# sch_knx-valve-control_v1_0.net
KiCad netlist of a schematic drawn in EasyEDA
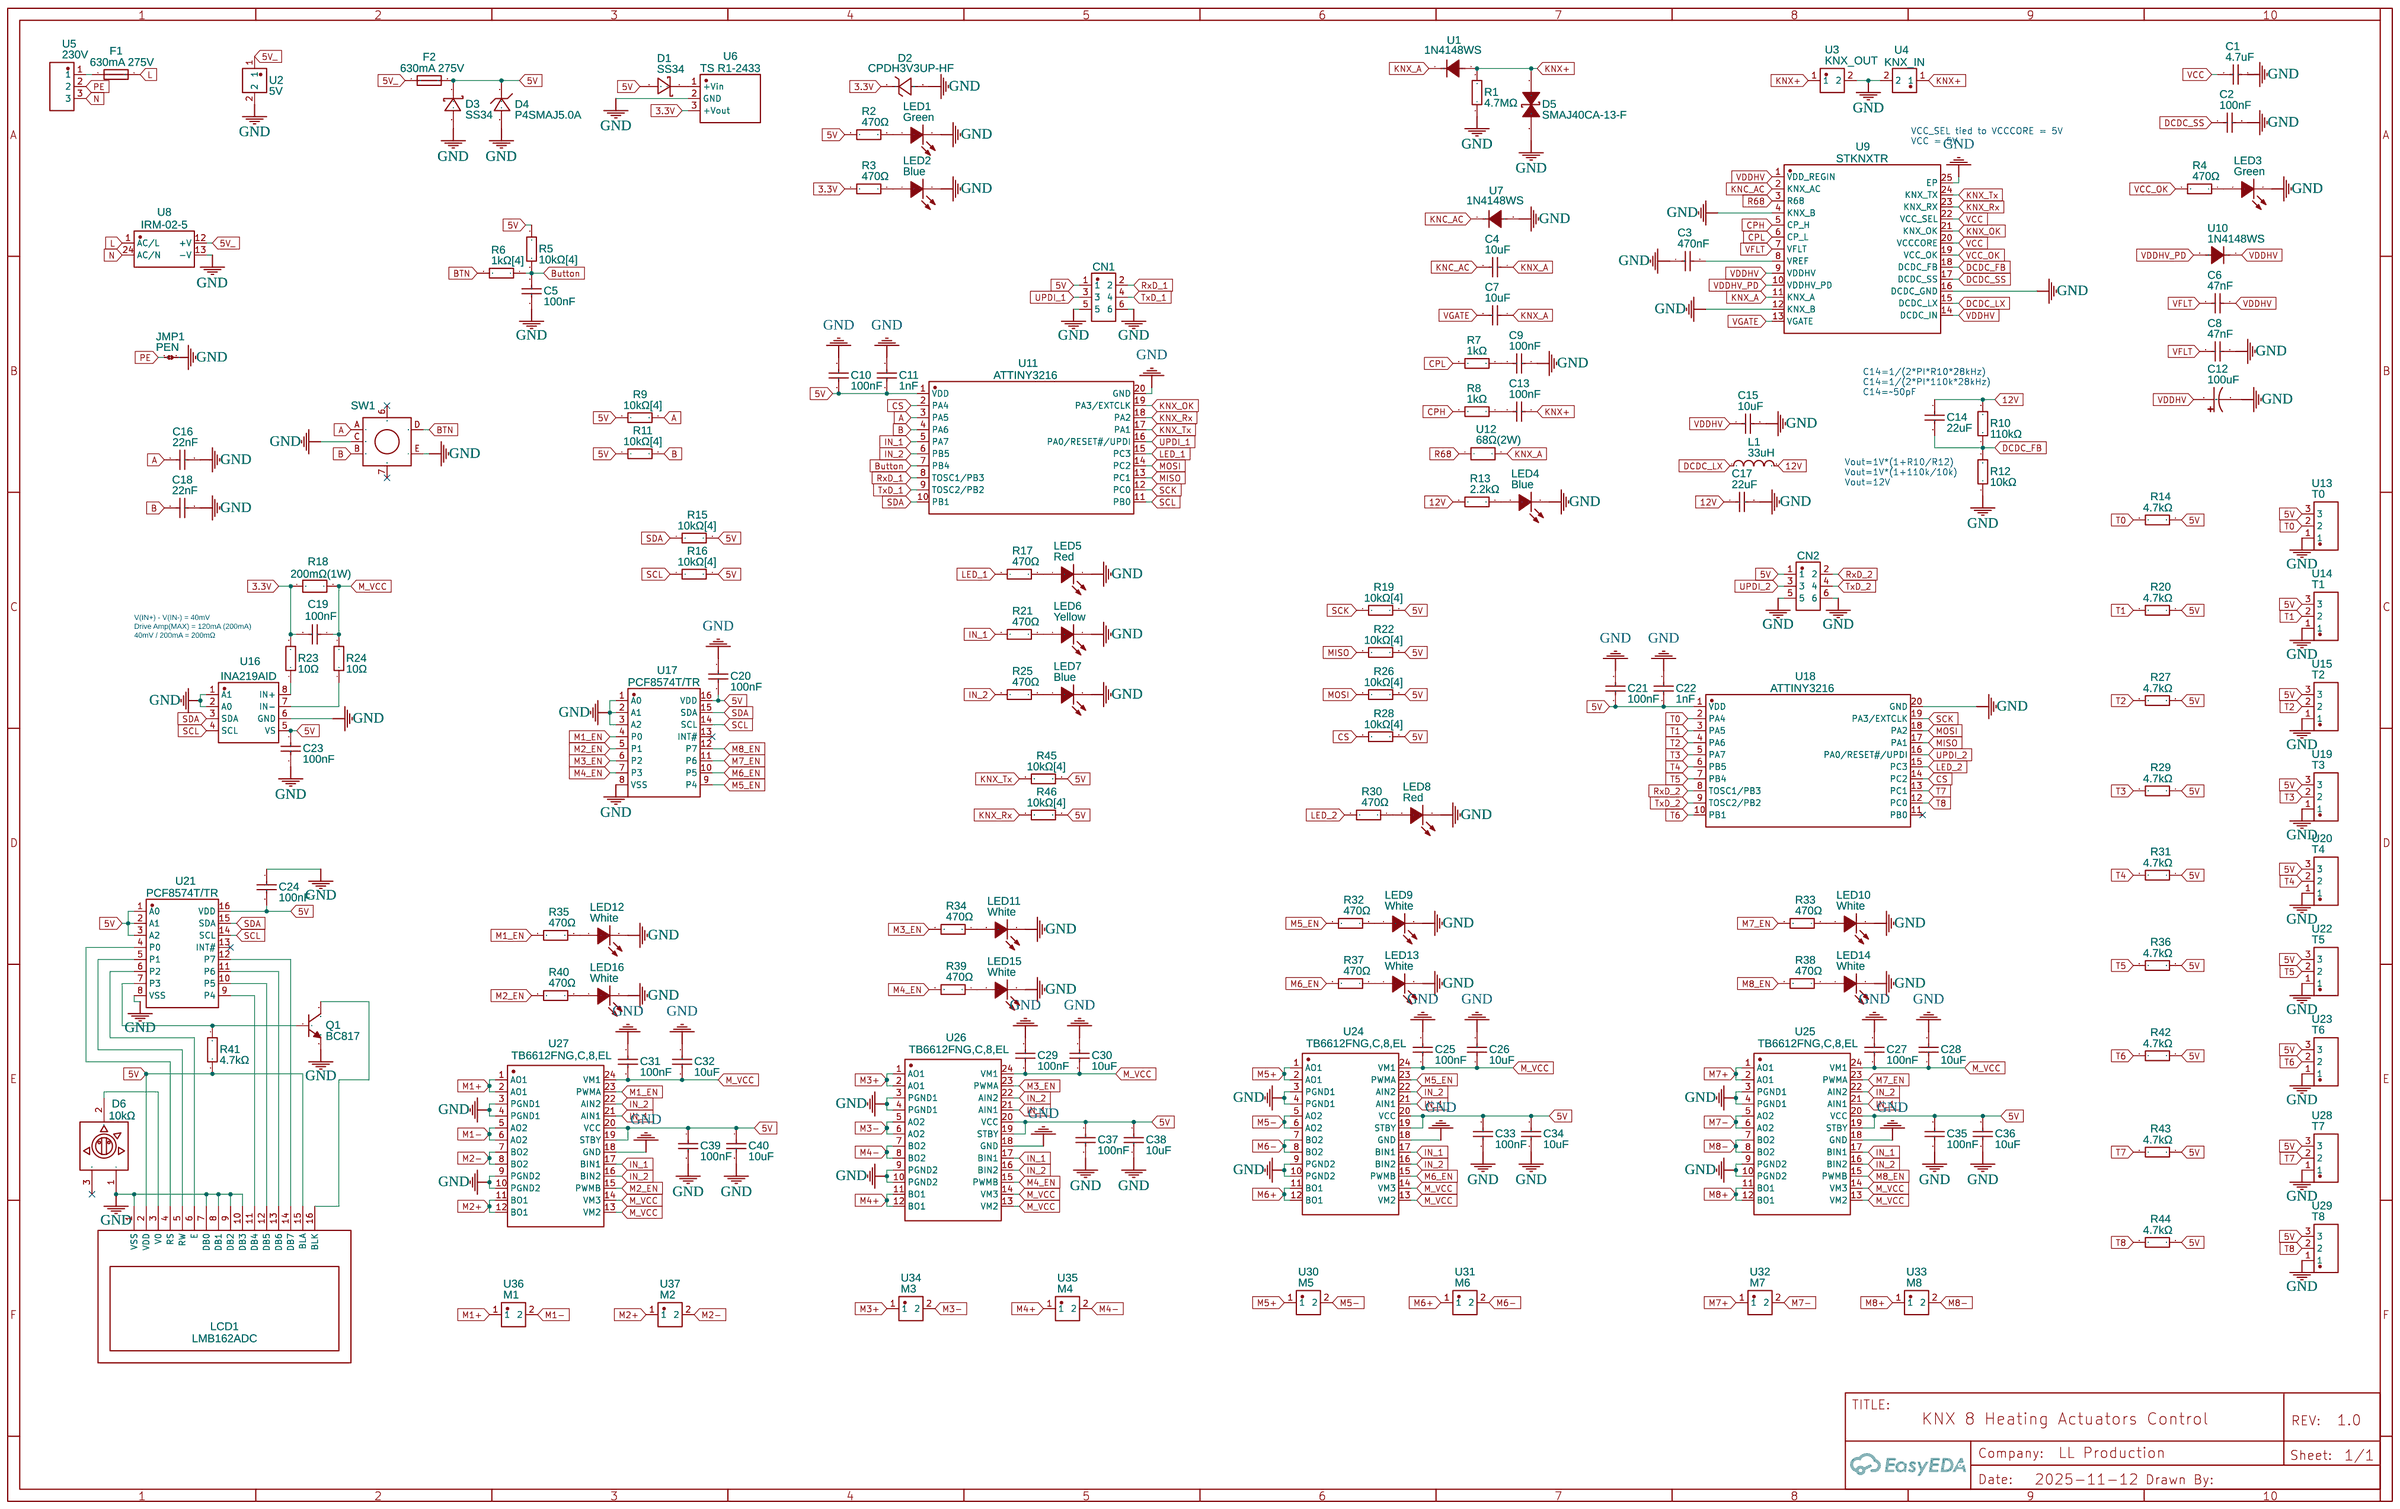
[diagram p0: schematic sheet]

(export (version "E")
  (design (tool "Eeschema 10.0.6"))
  (components
    (comp (ref "C1")
      (value "4.7uF")
      (fields (field (name "Manufacturer Part") "CC0603KRX7R9BB103") (field (name "Manufacturer") "YAGEO"))
      (libsource (lib "") (part "CC0603KRX7R9BB103_1"))
    )
    (comp (ref "C2")
      (value "100nF")
      (fields (field (name "Manufacturer Part") "CC0603KRX7R9BB103") (field (name "Manufacturer") "YAGEO"))
      (libsource (lib "") (part "CC0603KRX7R9BB103_3"))
    )
    (comp (ref "C3")
      (value "470nF")
      (fields (field (name "Manufacturer Part") "CC0603KRX7R9BB103") (field (name "Manufacturer") "YAGEO"))
      (libsource (lib "") (part "CC0603KRX7R9BB103_3"))
    )
    (comp (ref "C4")
      (value "10uF")
      (fields (field (name "Manufacturer Part") "CC0603KRX7R9BB103") (field (name "Manufacturer") "YAGEO"))
      (libsource (lib "") (part "CC0603KRX7R9BB103_1"))
    )
    (comp (ref "C5")
      (value "100nF")
      (fields (field (name "Manufacturer Part") "CC0603KRX7R9BB103") (field (name "Manufacturer") "YAGEO"))
      (libsource (lib "") (part "CC0603KRX7R9BB103_2"))
    )
    (comp (ref "C6")
      (value "47nF")
      (fields (field (name "Manufacturer Part") "CC0603KRX7R9BB103") (field (name "Manufacturer") "YAGEO"))
      (libsource (lib "") (part "CC0603KRX7R9BB103_1"))
    )
    (comp (ref "C7")
      (value "10uF")
      (fields (field (name "Manufacturer Part") "CC0603KRX7R9BB103") (field (name "Manufacturer") "YAGEO"))
      (libsource (lib "") (part "CC0603KRX7R9BB103_1"))
    )
    (comp (ref "C8")
      (value "47nF")
      (fields (field (name "Manufacturer Part") "CC0603KRX7R9BB103") (field (name "Manufacturer") "YAGEO"))
      (libsource (lib "") (part "CC0603KRX7R9BB103_1"))
    )
    (comp (ref "C9")
      (value "100nF")
      (fields (field (name "Manufacturer Part") "CC0603KRX7R9BB103") (field (name "Manufacturer") "YAGEO"))
      (libsource (lib "") (part "CC0603KRX7R9BB103_1"))
    )
    (comp (ref "C10")
      (value "100nF")
      (fields (field (name "Manufacturer Part") "CC0603KRX7R9BB103") (field (name "Manufacturer") "YAGEO"))
      (libsource (lib "") (part "CC0603KRX7R9BB103"))
    )
    (comp (ref "C11")
      (value "1nF")
      (fields (field (name "Manufacturer Part") "CC0603KRX7R9BB103") (field (name "Manufacturer") "YAGEO"))
      (libsource (lib "") (part "CC0603KRX7R9BB103"))
    )
    (comp (ref "C12")
      (value "100uF")
      (fields (field (name "Manufacturer Part") "VEJ101M1HTR-0810") (field (name "Manufacturer") "Lelon(立隆)"))
      (libsource (lib "") (part "VEJ101M1HTR-0810"))
    )
    (comp (ref "C13")
      (value "100nF")
      (fields (field (name "Manufacturer Part") "CC0603KRX7R9BB103") (field (name "Manufacturer") "YAGEO"))
      (libsource (lib "") (part "CC0603KRX7R9BB103_1"))
    )
    (comp (ref "C14")
      (value "22uF")
      (fields (field (name "Manufacturer Part") "CC0603KRX7R9BB103") (field (name "Manufacturer") "YAGEO"))
      (libsource (lib "") (part "CC0603KRX7R9BB103_2"))
    )
    (comp (ref "C15")
      (value "10uF")
      (fields (field (name "Manufacturer Part") "CC0603KRX7R9BB103") (field (name "Manufacturer") "YAGEO"))
      (libsource (lib "") (part "CC0603KRX7R9BB103_3"))
    )
    (comp (ref "C16")
      (value "22nF")
      (fields (field (name "Manufacturer Part") "CC0603KRX7R9BB103") (field (name "Manufacturer") "YAGEO"))
      (libsource (lib "") (part "CC0603KRX7R9BB103_1"))
    )
    (comp (ref "C17")
      (value "22uF")
      (fields (field (name "Manufacturer Part") "CC0603KRX7R9BB103") (field (name "Manufacturer") "YAGEO"))
      (libsource (lib "") (part "CC0603KRX7R9BB103_3"))
    )
    (comp (ref "C18")
      (value "22nF")
      (fields (field (name "Manufacturer Part") "CC0603KRX7R9BB103") (field (name "Manufacturer") "YAGEO"))
      (libsource (lib "") (part "CC0603KRX7R9BB103_1"))
    )
    (comp (ref "C19")
      (value "100nF")
      (fields (field (name "Manufacturer Part") "CC0603KRX7R9BB103") (field (name "Manufacturer") "YAGEO"))
      (libsource (lib "") (part "CC0603KRX7R9BB103_1"))
    )
    (comp (ref "C20")
      (value "100nF")
      (fields (field (name "Manufacturer Part") "CC0603KRX7R9BB103") (field (name "Manufacturer") "YAGEO"))
      (libsource (lib "") (part "CC0603KRX7R9BB103_2"))
    )
    (comp (ref "C21")
      (value "100nF")
      (fields (field (name "Manufacturer Part") "CC0603KRX7R9BB103") (field (name "Manufacturer") "YAGEO"))
      (libsource (lib "") (part "CC0603KRX7R9BB103"))
    )
    (comp (ref "C22")
      (value "1nF")
      (fields (field (name "Manufacturer Part") "CC0603KRX7R9BB103") (field (name "Manufacturer") "YAGEO"))
      (libsource (lib "") (part "CC0603KRX7R9BB103"))
    )
    (comp (ref "C23")
      (value "100nF")
      (fields (field (name "Manufacturer Part") "CC0603KRX7R9BB103") (field (name "Manufacturer") "YAGEO"))
      (libsource (lib "") (part "CC0603KRX7R9BB103_2"))
    )
    (comp (ref "C24")
      (value "100nF")
      (fields (field (name "Manufacturer Part") "CC0603KRX7R9BB103") (field (name "Manufacturer") "YAGEO"))
      (libsource (lib "") (part "CC0603KRX7R9BB103_2"))
    )
    (comp (ref "C25")
      (value "100nF")
      (fields (field (name "Manufacturer Part") "CC0603KRX7R9BB103") (field (name "Manufacturer") "YAGEO"))
      (libsource (lib "") (part "CC0603KRX7R9BB103_2"))
    )
    (comp (ref "C26")
      (value "10uF")
      (fields (field (name "Manufacturer Part") "CC0603KRX7R9BB103") (field (name "Manufacturer") "YAGEO"))
      (libsource (lib "") (part "CC0603KRX7R9BB103_2"))
    )
    (comp (ref "C27")
      (value "100nF")
      (fields (field (name "Manufacturer Part") "CC0603KRX7R9BB103") (field (name "Manufacturer") "YAGEO"))
      (libsource (lib "") (part "CC0603KRX7R9BB103_2"))
    )
    (comp (ref "C28")
      (value "10uF")
      (fields (field (name "Manufacturer Part") "CC0603KRX7R9BB103") (field (name "Manufacturer") "YAGEO"))
      (libsource (lib "") (part "CC0603KRX7R9BB103_2"))
    )
    (comp (ref "C29")
      (value "100nF")
      (fields (field (name "Manufacturer Part") "CC0603KRX7R9BB103") (field (name "Manufacturer") "YAGEO"))
      (libsource (lib "") (part "CC0603KRX7R9BB103_2"))
    )
    (comp (ref "C30")
      (value "10uF")
      (fields (field (name "Manufacturer Part") "CC0603KRX7R9BB103") (field (name "Manufacturer") "YAGEO"))
      (libsource (lib "") (part "CC0603KRX7R9BB103_2"))
    )
    (comp (ref "C31")
      (value "100nF")
      (fields (field (name "Manufacturer Part") "CC0603KRX7R9BB103") (field (name "Manufacturer") "YAGEO"))
      (libsource (lib "") (part "CC0603KRX7R9BB103_2"))
    )
    (comp (ref "C32")
      (value "10uF")
      (fields (field (name "Manufacturer Part") "CC0603KRX7R9BB103") (field (name "Manufacturer") "YAGEO"))
      (libsource (lib "") (part "CC0603KRX7R9BB103_2"))
    )
    (comp (ref "C33")
      (value "100nF")
      (fields (field (name "Manufacturer Part") "CC0603KRX7R9BB103") (field (name "Manufacturer") "YAGEO"))
      (libsource (lib "") (part "CC0603KRX7R9BB103_2"))
    )
    (comp (ref "C34")
      (value "10uF")
      (fields (field (name "Manufacturer Part") "CC0603KRX7R9BB103") (field (name "Manufacturer") "YAGEO"))
      (libsource (lib "") (part "CC0603KRX7R9BB103_2"))
    )
    (comp (ref "C35")
      (value "100nF")
      (fields (field (name "Manufacturer Part") "CC0603KRX7R9BB103") (field (name "Manufacturer") "YAGEO"))
      (libsource (lib "") (part "CC0603KRX7R9BB103_2"))
    )
    (comp (ref "C36")
      (value "10uF")
      (fields (field (name "Manufacturer Part") "CC0603KRX7R9BB103") (field (name "Manufacturer") "YAGEO"))
      (libsource (lib "") (part "CC0603KRX7R9BB103_2"))
    )
    (comp (ref "C37")
      (value "100nF")
      (fields (field (name "Manufacturer Part") "CC0603KRX7R9BB103") (field (name "Manufacturer") "YAGEO"))
      (libsource (lib "") (part "CC0603KRX7R9BB103_2"))
    )
    (comp (ref "C38")
      (value "10uF")
      (fields (field (name "Manufacturer Part") "CC0603KRX7R9BB103") (field (name "Manufacturer") "YAGEO"))
      (libsource (lib "") (part "CC0603KRX7R9BB103_2"))
    )
    (comp (ref "C39")
      (value "100nF")
      (fields (field (name "Manufacturer Part") "CC0603KRX7R9BB103") (field (name "Manufacturer") "YAGEO"))
      (libsource (lib "") (part "CC0603KRX7R9BB103_2"))
    )
    (comp (ref "C40")
      (value "10uF")
      (fields (field (name "Manufacturer Part") "CC0603KRX7R9BB103") (field (name "Manufacturer") "YAGEO"))
      (libsource (lib "") (part "CC0603KRX7R9BB103_2"))
    )
    (comp (ref "CN1")
      (value "321006SG0ABK00A01")
      (fields (field (name "Manufacturer") "JILN(锦凌)"))
      (libsource (lib "") (part "321006SG0ABK00A01"))
    )
    (comp (ref "CN2")
      (value "321006SG0ABK00A01")
      (fields (field (name "Manufacturer") "JILN(锦凌)"))
      (libsource (lib "") (part "321006SG0ABK00A01"))
    )
    (comp (ref "D1")
      (value "SS34")
      (fields (field (name "Manufacturer") "MDD"))
      (libsource (lib "") (part "SS34_C8678_1"))
    )
    (comp (ref "D2")
      (value "CPDH3V3UP-HF")
      (fields (field (name "Manufacturer Part") "SOD-523"))
      (libsource (lib "") (part "SOD-523"))
    )
    (comp (ref "D3")
      (value "SS34")
      (fields (field (name "Manufacturer") "MDD"))
      (libsource (lib "") (part "SS34_C8678"))
    )
    (comp (ref "D4")
      (value "P4SMAJ5.0A")
      (fields
        (field (name "Manufacturer Part") "P4SMAJ12A_R1_00001")
        (field (name "Manufacturer") "PANJIT(强茂)")
      )
      (libsource (lib "") (part "P4SMAJ12A-PEC"))
    )
    (comp (ref "D5")
      (value "SMAJ40CA-13-F")
      (fields (field (name "Manufacturer") "DIODES(美台)"))
      (libsource (lib "") (part "SMAJ40CA-13-F"))
    )
    (comp (ref "D6")
      (value "10kΩ")
      (fields (field (name "Manufacturer Part") "3314G-1-103E") (field (name "Manufacturer") "BOURNS"))
      (libsource (lib "") (part "3314G-1-103E"))
    )
    (comp (ref "F1")
      (value "630mA 275V")
      (fields (field (name "Manufacturer Part") "S1032-F-60.0A") (field (name "Manufacturer") "SART(萨特)"))
      (libsource (lib "") (part "S1032-F-60.0A"))
    )
    (comp (ref "F2")
      (value "630mA 275V")
      (fields (field (name "Manufacturer Part") "S1032-F-60.0A") (field (name "Manufacturer") "SART(萨特)"))
      (libsource (lib "") (part "S1032-F-60.0A"))
    )
    (comp (ref "JMP1") (value "PEN") (libsource (lib "") (part "JMP-2-NO-0603")))
    (comp (ref "L1")
      (value "33uH")
      (fields
        (field (name "Manufacturer Part") "NR5040T330M")
        (field (name "Manufacturer") "TAIYO YUDEN(太诱)")
      )
      (libsource (lib "") (part "NR5040T330M"))
    )
    (comp (ref "LCD1")
      (value "LMB162ADC")
      (fields (field (name "Manufacturer") "TOPWAY"))
      (libsource (lib "") (part "LMB162ADC"))
    )
    (comp (ref "LED1")
      (value "Green")
      (fields (field (name "Manufacturer Part") "SZYY0603R") (field (name "Manufacturer") "yongyu(永裕光电)"))
      (libsource (lib "") (part "SZYY0603R"))
    )
    (comp (ref "LED2")
      (value "Blue")
      (fields (field (name "Manufacturer Part") "SZYY0603R") (field (name "Manufacturer") "yongyu(永裕光电)"))
      (libsource (lib "") (part "SZYY0603R"))
    )
    (comp (ref "LED3")
      (value "Green")
      (fields (field (name "Manufacturer Part") "SZYY0603R") (field (name "Manufacturer") "yongyu(永裕光电)"))
      (libsource (lib "") (part "SZYY0603R"))
    )
    (comp (ref "LED4")
      (value "Blue")
      (fields (field (name "Manufacturer Part") "SZYY0603R") (field (name "Manufacturer") "yongyu(永裕光电)"))
      (libsource (lib "") (part "SZYY0603R"))
    )
    (comp (ref "LED5")
      (value "Red")
      (fields (field (name "Manufacturer Part") "SZYY0603R") (field (name "Manufacturer") "yongyu(永裕光电)"))
      (libsource (lib "") (part "SZYY0603R"))
    )
    (comp (ref "LED6")
      (value "Yellow")
      (fields (field (name "Manufacturer Part") "SZYY0603R") (field (name "Manufacturer") "yongyu(永裕光电)"))
      (libsource (lib "") (part "SZYY0603R"))
    )
    (comp (ref "LED7")
      (value "Blue")
      (fields (field (name "Manufacturer Part") "SZYY0603R") (field (name "Manufacturer") "yongyu(永裕光电)"))
      (libsource (lib "") (part "SZYY0603R"))
    )
    (comp (ref "LED8")
      (value "Red")
      (fields (field (name "Manufacturer Part") "SZYY0603R") (field (name "Manufacturer") "yongyu(永裕光电)"))
      (libsource (lib "") (part "SZYY0603R"))
    )
    (comp (ref "LED9")
      (value "White")
      (fields (field (name "Manufacturer Part") "SZYY0603R") (field (name "Manufacturer") "yongyu(永裕光电)"))
      (libsource (lib "") (part "SZYY0603R"))
    )
    (comp (ref "LED10")
      (value "White")
      (fields (field (name "Manufacturer Part") "SZYY0603R") (field (name "Manufacturer") "yongyu(永裕光电)"))
      (libsource (lib "") (part "SZYY0603R"))
    )
    (comp (ref "LED11")
      (value "White")
      (fields (field (name "Manufacturer Part") "SZYY0603R") (field (name "Manufacturer") "yongyu(永裕光电)"))
      (libsource (lib "") (part "SZYY0603R"))
    )
    (comp (ref "LED12")
      (value "White")
      (fields (field (name "Manufacturer Part") "SZYY0603R") (field (name "Manufacturer") "yongyu(永裕光电)"))
      (libsource (lib "") (part "SZYY0603R"))
    )
    (comp (ref "LED13")
      (value "White")
      (fields (field (name "Manufacturer Part") "SZYY0603R") (field (name "Manufacturer") "yongyu(永裕光电)"))
      (libsource (lib "") (part "SZYY0603R"))
    )
    (comp (ref "LED14")
      (value "White")
      (fields (field (name "Manufacturer Part") "SZYY0603R") (field (name "Manufacturer") "yongyu(永裕光电)"))
      (libsource (lib "") (part "SZYY0603R"))
    )
    (comp (ref "LED15")
      (value "White")
      (fields (field (name "Manufacturer Part") "SZYY0603R") (field (name "Manufacturer") "yongyu(永裕光电)"))
      (libsource (lib "") (part "SZYY0603R"))
    )
    (comp (ref "LED16")
      (value "White")
      (fields (field (name "Manufacturer Part") "SZYY0603R") (field (name "Manufacturer") "yongyu(永裕光电)"))
      (libsource (lib "") (part "SZYY0603R"))
    )
    (comp (ref "Q1")
      (value "BC817")
      (fields (field (name "Manufacturer Part") "BC817-40,215") (field (name "Manufacturer") "Nexperia(安世)"))
      (libsource (lib "") (part "BC817-40,215"))
    )
    (comp (ref "R1")
      (value "4.7MΩ")
      (fields (field (name "Manufacturer Part") "CR0603FA1001G") (field (name "Manufacturer") "LIZ(丽智电子)"))
      (libsource (lib "") (part "CR0603FA1001G_C126900_1"))
    )
    (comp (ref "R2")
      (value "470Ω")
      (fields (field (name "Manufacturer Part") "CR0603FA1001G") (field (name "Manufacturer") "LIZ(丽智电子)"))
      (libsource (lib "") (part "CR0603FA1001G_C126900"))
    )
    (comp (ref "R3")
      (value "470Ω")
      (fields (field (name "Manufacturer Part") "CR0603FA1001G") (field (name "Manufacturer") "LIZ(丽智电子)"))
      (libsource (lib "") (part "CR0603FA1001G_C126900"))
    )
    (comp (ref "R4")
      (value "470Ω")
      (fields (field (name "Manufacturer Part") "CR0603FA1001G") (field (name "Manufacturer") "LIZ(丽智电子)"))
      (libsource (lib "") (part "CR0603FA1001G_C126900"))
    )
    (comp (ref "R5")
      (value "10kΩ[4]")
      (fields
        (field (name "Manufacturer Part") "0402WGF1002TCE")
        (field (name "Manufacturer") "UNI-ROYAL(厚声)")
      )
      (libsource (lib "") (part "0402WGF1002TCE_2"))
    )
    (comp (ref "R6")
      (value "1kΩ[4]")
      (fields
        (field (name "Manufacturer Part") "0402WGF1002TCE")
        (field (name "Manufacturer") "UNI-ROYAL(厚声)")
      )
      (libsource (lib "") (part "0402WGF1002TCE_1"))
    )
    (comp (ref "R7")
      (value "1kΩ")
      (fields (field (name "Manufacturer Part") "CR0603FA1001G") (field (name "Manufacturer") "LIZ(丽智电子)"))
      (libsource (lib "") (part "CR0603FA1001G_C126900"))
    )
    (comp (ref "R8")
      (value "1kΩ")
      (fields (field (name "Manufacturer Part") "CR0603FA1001G") (field (name "Manufacturer") "LIZ(丽智电子)"))
      (libsource (lib "") (part "CR0603FA1001G_C126900"))
    )
    (comp (ref "R9")
      (value "10kΩ[4]")
      (fields
        (field (name "Manufacturer Part") "0402WGF1002TCE")
        (field (name "Manufacturer") "UNI-ROYAL(厚声)")
      )
      (libsource (lib "") (part "0402WGF1002TCE"))
    )
    (comp (ref "R10")
      (value "110kΩ")
      (fields (field (name "Manufacturer Part") "CR0603FA1001G") (field (name "Manufacturer") "LIZ(丽智电子)"))
      (libsource (lib "") (part "CR0603FA1001G_C126900_1"))
    )
    (comp (ref "R11")
      (value "10kΩ[4]")
      (fields
        (field (name "Manufacturer Part") "0402WGF1002TCE")
        (field (name "Manufacturer") "UNI-ROYAL(厚声)")
      )
      (libsource (lib "") (part "0402WGF1002TCE"))
    )
    (comp (ref "R12")
      (value "10kΩ")
      (fields (field (name "Manufacturer Part") "CR0603FA1001G") (field (name "Manufacturer") "LIZ(丽智电子)"))
      (libsource (lib "") (part "CR0603FA1001G_C126900_1"))
    )
    (comp (ref "R13")
      (value "2.2kΩ")
      (fields (field (name "Manufacturer Part") "CR0603FA1001G") (field (name "Manufacturer") "LIZ(丽智电子)"))
      (libsource (lib "") (part "CR0603FA1001G_C126900"))
    )
    (comp (ref "R14")
      (value "4.7kΩ")
      (fields (field (name "Manufacturer Part") "CR0603FA1001G") (field (name "Manufacturer") "LIZ(丽智电子)"))
      (libsource (lib "") (part "CR0603FA1001G_C126900"))
    )
    (comp (ref "R15")
      (value "10kΩ[4]")
      (fields
        (field (name "Manufacturer Part") "0402WGF1002TCE")
        (field (name "Manufacturer") "UNI-ROYAL(厚声)")
      )
      (libsource (lib "") (part "0402WGF1002TCE"))
    )
    (comp (ref "R16")
      (value "10kΩ[4]")
      (fields
        (field (name "Manufacturer Part") "0402WGF1002TCE")
        (field (name "Manufacturer") "UNI-ROYAL(厚声)")
      )
      (libsource (lib "") (part "0402WGF1002TCE"))
    )
    (comp (ref "R17")
      (value "470Ω")
      (fields (field (name "Manufacturer Part") "CR0603FA1001G") (field (name "Manufacturer") "LIZ(丽智电子)"))
      (libsource (lib "") (part "CR0603FA1001G_C126900"))
    )
    (comp (ref "R18")
      (value "200mΩ(1W)")
      (fields (field (name "Manufacturer Part") "SCR1206F1M1") (field (name "Manufacturer") "VO(翔胜)"))
      (libsource (lib "") (part "SCR1206F1M1"))
    )
    (comp (ref "R19")
      (value "10kΩ[4]")
      (fields
        (field (name "Manufacturer Part") "0402WGF1002TCE")
        (field (name "Manufacturer") "UNI-ROYAL(厚声)")
      )
      (libsource (lib "") (part "0402WGF1002TCE"))
    )
    (comp (ref "R20")
      (value "4.7kΩ")
      (fields (field (name "Manufacturer Part") "CR0603FA1001G") (field (name "Manufacturer") "LIZ(丽智电子)"))
      (libsource (lib "") (part "CR0603FA1001G_C126900"))
    )
    (comp (ref "R21")
      (value "470Ω")
      (fields (field (name "Manufacturer Part") "CR0603FA1001G") (field (name "Manufacturer") "LIZ(丽智电子)"))
      (libsource (lib "") (part "CR0603FA1001G_C126900"))
    )
    (comp (ref "R22")
      (value "10kΩ[4]")
      (fields
        (field (name "Manufacturer Part") "0402WGF1002TCE")
        (field (name "Manufacturer") "UNI-ROYAL(厚声)")
      )
      (libsource (lib "") (part "0402WGF1002TCE"))
    )
    (comp (ref "R23")
      (value "10Ω")
      (fields (field (name "Manufacturer Part") "CR0603FA1001G") (field (name "Manufacturer") "LIZ(丽智电子)"))
      (libsource (lib "") (part "CR0603FA1001G_C126900_1"))
    )
    (comp (ref "R24")
      (value "10Ω")
      (fields (field (name "Manufacturer Part") "CR0603FA1001G") (field (name "Manufacturer") "LIZ(丽智电子)"))
      (libsource (lib "") (part "CR0603FA1001G_C126900_1"))
    )
    (comp (ref "R25")
      (value "470Ω")
      (fields (field (name "Manufacturer Part") "CR0603FA1001G") (field (name "Manufacturer") "LIZ(丽智电子)"))
      (libsource (lib "") (part "CR0603FA1001G_C126900"))
    )
    (comp (ref "R26")
      (value "10kΩ[4]")
      (fields
        (field (name "Manufacturer Part") "0402WGF1002TCE")
        (field (name "Manufacturer") "UNI-ROYAL(厚声)")
      )
      (libsource (lib "") (part "0402WGF1002TCE"))
    )
    (comp (ref "R27")
      (value "4.7kΩ")
      (fields (field (name "Manufacturer Part") "CR0603FA1001G") (field (name "Manufacturer") "LIZ(丽智电子)"))
      (libsource (lib "") (part "CR0603FA1001G_C126900"))
    )
    (comp (ref "R28")
      (value "10kΩ[4]")
      (fields
        (field (name "Manufacturer Part") "0402WGF1002TCE")
        (field (name "Manufacturer") "UNI-ROYAL(厚声)")
      )
      (libsource (lib "") (part "0402WGF1002TCE"))
    )
    (comp (ref "R29")
      (value "4.7kΩ")
      (fields (field (name "Manufacturer Part") "CR0603FA1001G") (field (name "Manufacturer") "LIZ(丽智电子)"))
      (libsource (lib "") (part "CR0603FA1001G_C126900"))
    )
    (comp (ref "R30")
      (value "470Ω")
      (fields (field (name "Manufacturer Part") "CR0603FA1001G") (field (name "Manufacturer") "LIZ(丽智电子)"))
      (libsource (lib "") (part "CR0603FA1001G_C126900"))
    )
    (comp (ref "R31")
      (value "4.7kΩ")
      (fields (field (name "Manufacturer Part") "CR0603FA1001G") (field (name "Manufacturer") "LIZ(丽智电子)"))
      (libsource (lib "") (part "CR0603FA1001G_C126900"))
    )
    (comp (ref "R32")
      (value "470Ω")
      (fields (field (name "Manufacturer Part") "CR0603FA1001G") (field (name "Manufacturer") "LIZ(丽智电子)"))
      (libsource (lib "") (part "CR0603FA1001G_C126900"))
    )
    (comp (ref "R33")
      (value "470Ω")
      (fields (field (name "Manufacturer Part") "CR0603FA1001G") (field (name "Manufacturer") "LIZ(丽智电子)"))
      (libsource (lib "") (part "CR0603FA1001G_C126900"))
    )
    (comp (ref "R34")
      (value "470Ω")
      (fields (field (name "Manufacturer Part") "CR0603FA1001G") (field (name "Manufacturer") "LIZ(丽智电子)"))
      (libsource (lib "") (part "CR0603FA1001G_C126900"))
    )
    (comp (ref "R35")
      (value "470Ω")
      (fields (field (name "Manufacturer Part") "CR0603FA1001G") (field (name "Manufacturer") "LIZ(丽智电子)"))
      (libsource (lib "") (part "CR0603FA1001G_C126900"))
    )
    (comp (ref "R36")
      (value "4.7kΩ")
      (fields (field (name "Manufacturer Part") "CR0603FA1001G") (field (name "Manufacturer") "LIZ(丽智电子)"))
      (libsource (lib "") (part "CR0603FA1001G_C126900"))
    )
    (comp (ref "R37")
      (value "470Ω")
      (fields (field (name "Manufacturer Part") "CR0603FA1001G") (field (name "Manufacturer") "LIZ(丽智电子)"))
      (libsource (lib "") (part "CR0603FA1001G_C126900"))
    )
    (comp (ref "R38")
      (value "470Ω")
      (fields (field (name "Manufacturer Part") "CR0603FA1001G") (field (name "Manufacturer") "LIZ(丽智电子)"))
      (libsource (lib "") (part "CR0603FA1001G_C126900"))
    )
    (comp (ref "R39")
      (value "470Ω")
      (fields (field (name "Manufacturer Part") "CR0603FA1001G") (field (name "Manufacturer") "LIZ(丽智电子)"))
      (libsource (lib "") (part "CR0603FA1001G_C126900"))
    )
    (comp (ref "R40")
      (value "470Ω")
      (fields (field (name "Manufacturer Part") "CR0603FA1001G") (field (name "Manufacturer") "LIZ(丽智电子)"))
      (libsource (lib "") (part "CR0603FA1001G_C126900"))
    )
    (comp (ref "R41")
      (value "4.7kΩ")
      (fields (field (name "Manufacturer Part") "CR0603FA1001G") (field (name "Manufacturer") "LIZ(丽智电子)"))
      (libsource (lib "") (part "CR0603FA1001G_C126900_2"))
    )
    (comp (ref "R42")
      (value "4.7kΩ")
      (fields (field (name "Manufacturer Part") "CR0603FA1001G") (field (name "Manufacturer") "LIZ(丽智电子)"))
      (libsource (lib "") (part "CR0603FA1001G_C126900"))
    )
    (comp (ref "R43")
      (value "4.7kΩ")
      (fields (field (name "Manufacturer Part") "CR0603FA1001G") (field (name "Manufacturer") "LIZ(丽智电子)"))
      (libsource (lib "") (part "CR0603FA1001G_C126900"))
    )
    (comp (ref "R44")
      (value "4.7kΩ")
      (fields (field (name "Manufacturer Part") "CR0603FA1001G") (field (name "Manufacturer") "LIZ(丽智电子)"))
      (libsource (lib "") (part "CR0603FA1001G_C126900"))
    )
    (comp (ref "R45")
      (value "10kΩ[4]")
      (fields
        (field (name "Manufacturer Part") "0402WGF1002TCE")
        (field (name "Manufacturer") "UNI-ROYAL(厚声)")
      )
      (libsource (lib "") (part "0402WGF1002TCE"))
    )
    (comp (ref "R46")
      (value "10kΩ[4]")
      (fields
        (field (name "Manufacturer Part") "0402WGF1002TCE")
        (field (name "Manufacturer") "UNI-ROYAL(厚声)")
      )
      (libsource (lib "") (part "0402WGF1002TCE"))
    )
    (comp (ref "SW1")
      (value "EC11L1525G01")
      (fields (field (name "Manufacturer") "ALPSALPINE(阿尔卑斯阿尔派)"))
      (libsource (lib "") (part "EC11L1525G01"))
    )
    (comp (ref "U1")
      (value "1N4148WS")
      (fields (field (name "Manufacturer") "Zhengxin(正芯)"))
      (libsource (lib "") (part "1N4148WS"))
    )
    (comp (ref "U2")
      (value "5V")
      (fields (field (name "Manufacturer Part") "2P,间距5.08mm,弹片压线升降式"))
      (libsource (lib "") (part "2P,间距5.08MM,弹片压线升降式_1"))
    )
    (comp (ref "U3")
      (value "KNX_OUT")
      (fields (field (name "Manufacturer Part") "2P,间距5.08mm,弹片压线升降式"))
      (libsource (lib "") (part "2P,间距5.08MM,弹片压线升降式"))
    )
    (comp (ref "U4")
      (value "KNX_IN")
      (fields (field (name "Manufacturer Part") "2P,间距5.08mm,弹片压线升降式"))
      (libsource (lib "") (part "2P,间距5.08MM,弹片压线升降式_2"))
    )
    (comp (ref "U5")
      (value "230V")
      (fields
        (field (name "Manufacturer Part") "DB127V-5.08-3P-GN-S")
        (field (name "Manufacturer") "DIBO(地博电气)")
      )
      (libsource (lib "") (part "DB127V-5.08-3P-GN-S_1"))
    )
    (comp (ref "U6")
      (value "TS R1-2433")
      (fields (field (name "Manufacturer") "TRACO POWER"))
      (libsource (lib "") (part "TS R1-2433"))
    )
    (comp (ref "U7")
      (value "1N4148WS")
      (fields (field (name "Manufacturer") "Zhengxin(正芯)"))
      (libsource (lib "") (part "1N4148WS"))
    )
    (comp (ref "U8")
      (value "IRM-02-5")
      (fields (field (name "Manufacturer") "MW(明纬)"))
      (libsource (lib "") (part "IRM-02-5"))
    )
    (comp (ref "U9")
      (value "STKNXTR")
      (fields (field (name "Manufacturer") "ST(意法半导体)"))
      (libsource (lib "") (part "STKNXTR"))
    )
    (comp (ref "U10")
      (value "1N4148WS")
      (fields (field (name "Manufacturer") "Zhengxin(正芯)"))
      (libsource (lib "") (part "1N4148WS_1"))
    )
    (comp (ref "U11")
      (value "ATTINY3216")
      (fields
        (field (name "Manufacturer Part") "ATTINY1616-SN")
        (field (name "Manufacturer") "MICROCHIP(美国微芯)")
      )
      (libsource (lib "") (part "ATTINY1616-SN_C614136"))
    )
    (comp (ref "U12")
      (value "68Ω(2W)")
      (fields
        (field (name "Manufacturer Part") "HoJLR2512-3W-3.5mR-1%")
        (field (name "Manufacturer") "Milliohm(毫欧)")
      )
      (libsource (lib "") (part "HOJLR2512-3W-3.5MR-1%"))
    )
    (comp (ref "U13")
      (value "T0")
      (fields
        (field (name "Manufacturer Part") "DB127V-5.08-3P-GN-S")
        (field (name "Manufacturer") "DIBO(地博电气)")
      )
      (libsource (lib "") (part "DB127V-5.08-3P-GN-S"))
    )
    (comp (ref "U14")
      (value "T1")
      (fields
        (field (name "Manufacturer Part") "DB127V-5.08-3P-GN-S")
        (field (name "Manufacturer") "DIBO(地博电气)")
      )
      (libsource (lib "") (part "DB127V-5.08-3P-GN-S"))
    )
    (comp (ref "U15")
      (value "T2")
      (fields
        (field (name "Manufacturer Part") "DB127V-5.08-3P-GN-S")
        (field (name "Manufacturer") "DIBO(地博电气)")
      )
      (libsource (lib "") (part "DB127V-5.08-3P-GN-S"))
    )
    (comp (ref "U16")
      (value "INA219AID")
      (fields (field (name "Manufacturer") "TI(德州仪器)"))
      (libsource (lib "") (part "INA219AID"))
    )
    (comp (ref "U17")
      (value "PCF8574T/TR")
      (fields (field (name "Manufacturer") "HGSEMI(华冠)"))
      (libsource (lib "") (part "PCF8574T/TR"))
    )
    (comp (ref "U18")
      (value "ATTINY3216")
      (fields
        (field (name "Manufacturer Part") "ATTINY1616-SN")
        (field (name "Manufacturer") "MICROCHIP(美国微芯)")
      )
      (libsource (lib "") (part "ATTINY1616-SN_C614136"))
    )
    (comp (ref "U19")
      (value "T3")
      (fields
        (field (name "Manufacturer Part") "DB127V-5.08-3P-GN-S")
        (field (name "Manufacturer") "DIBO(地博电气)")
      )
      (libsource (lib "") (part "DB127V-5.08-3P-GN-S"))
    )
    (comp (ref "U20")
      (value "T4")
      (fields
        (field (name "Manufacturer Part") "DB127V-5.08-3P-GN-S")
        (field (name "Manufacturer") "DIBO(地博电气)")
      )
      (libsource (lib "") (part "DB127V-5.08-3P-GN-S"))
    )
    (comp (ref "U21")
      (value "PCF8574T/TR")
      (fields (field (name "Manufacturer") "HGSEMI(华冠)"))
      (libsource (lib "") (part "PCF8574T/TR"))
    )
    (comp (ref "U22")
      (value "T5")
      (fields
        (field (name "Manufacturer Part") "DB127V-5.08-3P-GN-S")
        (field (name "Manufacturer") "DIBO(地博电气)")
      )
      (libsource (lib "") (part "DB127V-5.08-3P-GN-S"))
    )
    (comp (ref "U23")
      (value "T6")
      (fields
        (field (name "Manufacturer Part") "DB127V-5.08-3P-GN-S")
        (field (name "Manufacturer") "DIBO(地博电气)")
      )
      (libsource (lib "") (part "DB127V-5.08-3P-GN-S"))
    )
    (comp (ref "U24")
      (value "TB6612FNG,C,8,EL")
      (fields (field (name "Manufacturer") "TOSHIBA(东芝)"))
      (libsource (lib "") (part "TB6612FNG,C,8,EL"))
    )
    (comp (ref "U25")
      (value "TB6612FNG,C,8,EL")
      (fields (field (name "Manufacturer") "TOSHIBA(东芝)"))
      (libsource (lib "") (part "TB6612FNG,C,8,EL"))
    )
    (comp (ref "U26")
      (value "TB6612FNG,C,8,EL")
      (fields (field (name "Manufacturer") "TOSHIBA(东芝)"))
      (libsource (lib "") (part "TB6612FNG,C,8,EL"))
    )
    (comp (ref "U27")
      (value "TB6612FNG,C,8,EL")
      (fields (field (name "Manufacturer") "TOSHIBA(东芝)"))
      (libsource (lib "") (part "TB6612FNG,C,8,EL"))
    )
    (comp (ref "U28")
      (value "T7")
      (fields
        (field (name "Manufacturer Part") "DB127V-5.08-3P-GN-S")
        (field (name "Manufacturer") "DIBO(地博电气)")
      )
      (libsource (lib "") (part "DB127V-5.08-3P-GN-S"))
    )
    (comp (ref "U29")
      (value "T8")
      (fields
        (field (name "Manufacturer Part") "DB127V-5.08-3P-GN-S")
        (field (name "Manufacturer") "DIBO(地博电气)")
      )
      (libsource (lib "") (part "DB127V-5.08-3P-GN-S"))
    )
    (comp (ref "U30")
      (value "M5")
      (fields (field (name "Manufacturer Part") "2P,间距5.08mm,弹片压线升降式"))
      (libsource (lib "") (part "2P,间距5.08MM,弹片压线升降式"))
    )
    (comp (ref "U31")
      (value "M6")
      (fields (field (name "Manufacturer Part") "2P,间距5.08mm,弹片压线升降式"))
      (libsource (lib "") (part "2P,间距5.08MM,弹片压线升降式"))
    )
    (comp (ref "U32")
      (value "M7")
      (fields (field (name "Manufacturer Part") "2P,间距5.08mm,弹片压线升降式"))
      (libsource (lib "") (part "2P,间距5.08MM,弹片压线升降式"))
    )
    (comp (ref "U33")
      (value "M8")
      (fields (field (name "Manufacturer Part") "2P,间距5.08mm,弹片压线升降式"))
      (libsource (lib "") (part "2P,间距5.08MM,弹片压线升降式"))
    )
    (comp (ref "U34")
      (value "M3")
      (fields (field (name "Manufacturer Part") "2P,间距5.08mm,弹片压线升降式"))
      (libsource (lib "") (part "2P,间距5.08MM,弹片压线升降式"))
    )
    (comp (ref "U35")
      (value "M4")
      (fields (field (name "Manufacturer Part") "2P,间距5.08mm,弹片压线升降式"))
      (libsource (lib "") (part "2P,间距5.08MM,弹片压线升降式"))
    )
    (comp (ref "U36")
      (value "M1")
      (fields (field (name "Manufacturer Part") "2P,间距5.08mm,弹片压线升降式"))
      (libsource (lib "") (part "2P,间距5.08MM,弹片压线升降式"))
    )
    (comp (ref "U37")
      (value "M2")
      (fields (field (name "Manufacturer Part") "2P,间距5.08mm,弹片压线升降式"))
      (libsource (lib "") (part "2P,间距5.08MM,弹片压线升降式"))
    )
  )
  (nets
    (net (code "1") (name "3.3V") (class "Default")
      (node (ref "C19") (pin "2") (pinfunction "2_2") (pintype "input"))
      (node (ref "D2") (pin "1") (pinfunction "K_1") (pintype "unspecified"))
      (node (ref "R18") (pin "1") (pinfunction "1_1") (pintype "unspecified"))
      (node (ref "R23") (pin "2") (pinfunction "2_2") (pintype "input"))
      (node (ref "R3") (pin "2") (pinfunction "2_2") (pintype "input"))
      (node (ref "U6") (pin "3") (pinfunction "+Vout_3") (pintype "unspecified"))
    )
    (net (code "2") (name "5V") (class "Default")
      (node (ref "C10") (pin "1") (pinfunction "1_1") (pintype "input"))
      (node (ref "C11") (pin "1") (pinfunction "1_1") (pintype "input"))
      (node (ref "C20") (pin "2") (pinfunction "2_2") (pintype "input"))
      (node (ref "C21") (pin "1") (pinfunction "1_1") (pintype "input"))
      (node (ref "C22") (pin "1") (pinfunction "1_1") (pintype "input"))
      (node (ref "C23") (pin "1") (pinfunction "1_1") (pintype "input"))
      (node (ref "C24") (pin "2") (pinfunction "2_2") (pintype "input"))
      (node (ref "C33") (pin "1") (pinfunction "1_1") (pintype "input"))
      (node (ref "C34") (pin "1") (pinfunction "1_1") (pintype "input"))
      (node (ref "C35") (pin "1") (pinfunction "1_1") (pintype "input"))
      (node (ref "C36") (pin "1") (pinfunction "1_1") (pintype "input"))
      (node (ref "C37") (pin "1") (pinfunction "1_1") (pintype "input"))
      (node (ref "C38") (pin "1") (pinfunction "1_1") (pintype "input"))
      (node (ref "C39") (pin "1") (pinfunction "1_1") (pintype "input"))
      (node (ref "C40") (pin "1") (pinfunction "1_1") (pintype "input"))
      (node (ref "CN1") (pin "1") (pinfunction "1_1") (pintype "unspecified"))
      (node (ref "CN2") (pin "1") (pinfunction "1_1") (pintype "unspecified"))
      (node (ref "D1") (pin "2") (pinfunction "A_2") (pintype "unspecified"))
      (node (ref "D3") (pin "1") (pinfunction "K_1") (pintype "unspecified"))
      (node (ref "D4") (pin "1") (pinfunction "C_1") (pintype "unspecified"))
      (node (ref "F2") (pin "2") (pinfunction "2_2") (pintype "unspecified"))
      (node (ref "LCD1") (pin "15") (pinfunction "BLA_15") (pintype "unspecified"))
      (node (ref "LCD1") (pin "2") (pinfunction "VDD_2") (pintype "unspecified"))
      (node (ref "R11") (pin "1") (pinfunction "1_1") (pintype "input"))
      (node (ref "R14") (pin "1") (pinfunction "1_1") (pintype "input"))
      (node (ref "R15") (pin "2") (pinfunction "2_2") (pintype "input"))
      (node (ref "R16") (pin "2") (pinfunction "2_2") (pintype "input"))
      (node (ref "R19") (pin "2") (pinfunction "2_2") (pintype "input"))
      (node (ref "R2") (pin "2") (pinfunction "2_2") (pintype "input"))
      (node (ref "R20") (pin "1") (pinfunction "1_1") (pintype "input"))
      (node (ref "R22") (pin "2") (pinfunction "2_2") (pintype "input"))
      (node (ref "R26") (pin "2") (pinfunction "2_2") (pintype "input"))
      (node (ref "R27") (pin "1") (pinfunction "1_1") (pintype "input"))
      (node (ref "R28") (pin "2") (pinfunction "2_2") (pintype "input"))
      (node (ref "R29") (pin "1") (pinfunction "1_1") (pintype "input"))
      (node (ref "R31") (pin "1") (pinfunction "1_1") (pintype "input"))
      (node (ref "R36") (pin "1") (pinfunction "1_1") (pintype "input"))
      (node (ref "R41") (pin "2") (pinfunction "2_2") (pintype "input"))
      (node (ref "R42") (pin "1") (pinfunction "1_1") (pintype "input"))
      (node (ref "R43") (pin "1") (pinfunction "1_1") (pintype "input"))
      (node (ref "R44") (pin "1") (pinfunction "1_1") (pintype "input"))
      (node (ref "R45") (pin "2") (pinfunction "2_2") (pintype "input"))
      (node (ref "R46") (pin "2") (pinfunction "2_2") (pintype "input"))
      (node (ref "R5") (pin "1") (pinfunction "1_1") (pintype "input"))
      (node (ref "R9") (pin "1") (pinfunction "1_1") (pintype "input"))
      (node (ref "U11") (pin "1") (pinfunction "VDD_1") (pintype "unspecified"))
      (node (ref "U13") (pin "3") (pinfunction "3_3") (pintype "unspecified"))
      (node (ref "U14") (pin "3") (pinfunction "3_3") (pintype "unspecified"))
      (node (ref "U15") (pin "3") (pinfunction "3_3") (pintype "unspecified"))
      (node (ref "U16") (pin "5") (pinfunction "VS_5") (pintype "unspecified"))
      (node (ref "U17") (pin "16") (pinfunction "VDD_16") (pintype "unspecified"))
      (node (ref "U18") (pin "1") (pinfunction "VDD_1") (pintype "unspecified"))
      (node (ref "U19") (pin "3") (pinfunction "3_3") (pintype "unspecified"))
      (node (ref "U20") (pin "3") (pinfunction "3_3") (pintype "unspecified"))
      (node (ref "U21") (pin "1") (pinfunction "A0_1") (pintype "unspecified"))
      (node (ref "U21") (pin "16") (pinfunction "VDD_16") (pintype "unspecified"))
      (node (ref "U21") (pin "2") (pinfunction "A1_2") (pintype "unspecified"))
      (node (ref "U21") (pin "3") (pinfunction "A2_3") (pintype "unspecified"))
      (node (ref "U22") (pin "3") (pinfunction "3_3") (pintype "unspecified"))
      (node (ref "U23") (pin "3") (pinfunction "3_3") (pintype "unspecified"))
      (node (ref "U24") (pin "19") (pinfunction "STBY_19") (pintype "unspecified"))
      (node (ref "U24") (pin "20") (pinfunction "VCC_20") (pintype "unspecified"))
      (node (ref "U25") (pin "19") (pinfunction "STBY_19") (pintype "unspecified"))
      (node (ref "U25") (pin "20") (pinfunction "VCC_20") (pintype "unspecified"))
      (node (ref "U26") (pin "19") (pinfunction "STBY_19") (pintype "unspecified"))
      (node (ref "U26") (pin "20") (pinfunction "VCC_20") (pintype "unspecified"))
      (node (ref "U27") (pin "19") (pinfunction "STBY_19") (pintype "unspecified"))
      (node (ref "U27") (pin "20") (pinfunction "VCC_20") (pintype "unspecified"))
      (node (ref "U28") (pin "3") (pinfunction "3_3") (pintype "unspecified"))
      (node (ref "U29") (pin "3") (pinfunction "3_3") (pintype "unspecified"))
    )
    (net (code "3") (name "5V_") (class "Default")
      (node (ref "F2") (pin "1") (pinfunction "1_1") (pintype "unspecified"))
      (node (ref "U2") (pin "1") (pinfunction "1_1") (pintype "unspecified"))
      (node (ref "U8") (pin "12") (pinfunction "+V_12") (pintype "unspecified"))
    )
    (net (code "4") (name "12V") (class "Default")
      (node (ref "C14") (pin "1") (pinfunction "1_1") (pintype "input"))
      (node (ref "C17") (pin "1") (pinfunction "1_1") (pintype "input"))
      (node (ref "L1") (pin "2") (pinfunction "2_2") (pintype "unspecified"))
      (node (ref "R10") (pin "2") (pinfunction "2_2") (pintype "input"))
      (node (ref "R13") (pin "2") (pinfunction "2_2") (pintype "input"))
    )
    (net (code "5") (name "A") (class "Default")
      (node (ref "C16") (pin "2") (pinfunction "2_2") (pintype "input"))
      (node (ref "R9") (pin "2") (pinfunction "2_2") (pintype "input"))
      (node (ref "SW1") (pin "A") (pinfunction "A_A") (pintype "unspecified"))
      (node (ref "U11") (pin "3") (pinfunction "PA5_3") (pintype "unspecified"))
    )
    (net (code "6") (name "B") (class "Default")
      (node (ref "C18") (pin "2") (pinfunction "2_2") (pintype "input"))
      (node (ref "R11") (pin "2") (pinfunction "2_2") (pintype "input"))
      (node (ref "SW1") (pin "B") (pinfunction "B_B") (pintype "unspecified"))
      (node (ref "U11") (pin "4") (pinfunction "PA6_4") (pintype "unspecified"))
    )
    (net (code "7") (name "BTN") (class "Default")
      (node (ref "R6") (pin "2") (pinfunction "2_2") (pintype "input"))
      (node (ref "SW1") (pin "D") (pinfunction "D_D") (pintype "unspecified"))
    )
    (net (code "8") (name "Button") (class "Default")
      (node (ref "C5") (pin "1") (pinfunction "1_1") (pintype "input"))
      (node (ref "R5") (pin "2") (pinfunction "2_2") (pintype "input"))
      (node (ref "R6") (pin "1") (pinfunction "1_1") (pintype "input"))
      (node (ref "U11") (pin "7") (pinfunction "PB4_7") (pintype "unspecified"))
    )
    (net (code "9") (name "CPH") (class "Default")
      (node (ref "R8") (pin "2") (pinfunction "2_2") (pintype "input"))
      (node (ref "U9") (pin "5") (pinfunction "CP_H_5") (pintype "unspecified"))
    )
    (net (code "10") (name "CPL") (class "Default")
      (node (ref "R7") (pin "2") (pinfunction "2_2") (pintype "input"))
      (node (ref "U9") (pin "6") (pinfunction "CP_L_6") (pintype "unspecified"))
    )
    (net (code "11") (name "CS") (class "Default")
      (node (ref "R28") (pin "1") (pinfunction "1_1") (pintype "input"))
      (node (ref "U11") (pin "2") (pinfunction "PA4_2") (pintype "unspecified"))
      (node (ref "U18") (pin "14") (pinfunction "PC2_14") (pintype "unspecified"))
    )
    (net (code "12") (name "DCDC_FB") (class "Default")
      (node (ref "C14") (pin "2") (pinfunction "2_2") (pintype "input"))
      (node (ref "R10") (pin "1") (pinfunction "1_1") (pintype "input"))
      (node (ref "R12") (pin "2") (pinfunction "2_2") (pintype "input"))
      (node (ref "U9") (pin "18") (pinfunction "DCDC_FB_18") (pintype "unspecified"))
    )
    (net (code "13") (name "DCDC_LX") (class "Default")
      (node (ref "L1") (pin "1") (pinfunction "1_1") (pintype "unspecified"))
      (node (ref "U9") (pin "15") (pinfunction "DCDC_LX_15") (pintype "unspecified"))
    )
    (net (code "14") (name "DCDC_SS") (class "Default")
      (node (ref "C2") (pin "1") (pinfunction "1_1") (pintype "input"))
      (node (ref "U9") (pin "17") (pinfunction "DCDC_SS_17") (pintype "unspecified"))
    )
    (net (code "15") (name "GND") (class "Default")
      (node (ref "C1") (pin "1") (pinfunction "1_1") (pintype "input"))
      (node (ref "C10") (pin "2") (pinfunction "2_2") (pintype "input"))
      (node (ref "C11") (pin "2") (pinfunction "2_2") (pintype "input"))
      (node (ref "C12") (pin "2") (pinfunction "2_2") (pintype "unspecified"))
      (node (ref "C15") (pin "2") (pinfunction "2_2") (pintype "input"))
      (node (ref "C16") (pin "1") (pinfunction "1_1") (pintype "input"))
      (node (ref "C17") (pin "2") (pinfunction "2_2") (pintype "input"))
      (node (ref "C18") (pin "1") (pinfunction "1_1") (pintype "input"))
      (node (ref "C2") (pin "2") (pinfunction "2_2") (pintype "input"))
      (node (ref "C20") (pin "1") (pinfunction "1_1") (pintype "input"))
      (node (ref "C21") (pin "2") (pinfunction "2_2") (pintype "input"))
      (node (ref "C22") (pin "2") (pinfunction "2_2") (pintype "input"))
      (node (ref "C23") (pin "2") (pinfunction "2_2") (pintype "input"))
      (node (ref "C24") (pin "1") (pinfunction "1_1") (pintype "input"))
      (node (ref "C25") (pin "1") (pinfunction "1_1") (pintype "input"))
      (node (ref "C26") (pin "1") (pinfunction "1_1") (pintype "input"))
      (node (ref "C27") (pin "1") (pinfunction "1_1") (pintype "input"))
      (node (ref "C28") (pin "1") (pinfunction "1_1") (pintype "input"))
      (node (ref "C29") (pin "1") (pinfunction "1_1") (pintype "input"))
      (node (ref "C3") (pin "1") (pinfunction "1_1") (pintype "input"))
      (node (ref "C30") (pin "1") (pinfunction "1_1") (pintype "input"))
      (node (ref "C31") (pin "1") (pinfunction "1_1") (pintype "input"))
      (node (ref "C32") (pin "1") (pinfunction "1_1") (pintype "input"))
      (node (ref "C33") (pin "2") (pinfunction "2_2") (pintype "input"))
      (node (ref "C34") (pin "2") (pinfunction "2_2") (pintype "input"))
      (node (ref "C35") (pin "2") (pinfunction "2_2") (pintype "input"))
      (node (ref "C36") (pin "2") (pinfunction "2_2") (pintype "input"))
      (node (ref "C37") (pin "2") (pinfunction "2_2") (pintype "input"))
      (node (ref "C38") (pin "2") (pinfunction "2_2") (pintype "input"))
      (node (ref "C39") (pin "2") (pinfunction "2_2") (pintype "input"))
      (node (ref "C40") (pin "2") (pinfunction "2_2") (pintype "input"))
      (node (ref "C5") (pin "2") (pinfunction "2_2") (pintype "input"))
      (node (ref "C8") (pin "1") (pinfunction "1_1") (pintype "input"))
      (node (ref "C9") (pin "1") (pinfunction "1_1") (pintype "input"))
      (node (ref "CN1") (pin "5") (pinfunction "5_5") (pintype "unspecified"))
      (node (ref "CN1") (pin "6") (pinfunction "6_6") (pintype "unspecified"))
      (node (ref "CN2") (pin "5") (pinfunction "5_5") (pintype "unspecified"))
      (node (ref "CN2") (pin "6") (pinfunction "6_6") (pintype "unspecified"))
      (node (ref "D2") (pin "2") (pinfunction "A_2") (pintype "unspecified"))
      (node (ref "D3") (pin "2") (pinfunction "A_2") (pintype "unspecified"))
      (node (ref "D4") (pin "2") (pinfunction "A_2") (pintype "unspecified"))
      (node (ref "D5") (pin "2") (pinfunction "2_2") (pintype "unspecified"))
      (node (ref "D6") (pin "1") (pinfunction "1_1") (pintype "unspecified"))
      (node (ref "JMP1") (pin "2") (pinfunction "2_2") (pintype "unspecified"))
      (node (ref "LCD1") (pin "1") (pinfunction "VSS_1") (pintype "unspecified"))
      (node (ref "LCD1") (pin "10") (pinfunction "DB3_10") (pintype "unspecified"))
      (node (ref "LCD1") (pin "7") (pinfunction "DB0_7") (pintype "unspecified"))
      (node (ref "LCD1") (pin "8") (pinfunction "DB1_8") (pintype "unspecified"))
      (node (ref "LCD1") (pin "9") (pinfunction "DB2_9") (pintype "unspecified"))
      (node (ref "LED1") (pin "2") (pinfunction "-_2") (pintype "unspecified"))
      (node (ref "LED10") (pin "2") (pinfunction "-_2") (pintype "unspecified"))
      (node (ref "LED11") (pin "2") (pinfunction "-_2") (pintype "unspecified"))
      (node (ref "LED12") (pin "2") (pinfunction "-_2") (pintype "unspecified"))
      (node (ref "LED13") (pin "2") (pinfunction "-_2") (pintype "unspecified"))
      (node (ref "LED14") (pin "2") (pinfunction "-_2") (pintype "unspecified"))
      (node (ref "LED15") (pin "2") (pinfunction "-_2") (pintype "unspecified"))
      (node (ref "LED16") (pin "2") (pinfunction "-_2") (pintype "unspecified"))
      (node (ref "LED2") (pin "2") (pinfunction "-_2") (pintype "unspecified"))
      (node (ref "LED3") (pin "2") (pinfunction "-_2") (pintype "unspecified"))
      (node (ref "LED4") (pin "2") (pinfunction "-_2") (pintype "unspecified"))
      (node (ref "LED5") (pin "2") (pinfunction "-_2") (pintype "unspecified"))
      (node (ref "LED6") (pin "2") (pinfunction "-_2") (pintype "unspecified"))
      (node (ref "LED7") (pin "2") (pinfunction "-_2") (pintype "unspecified"))
      (node (ref "LED8") (pin "2") (pinfunction "-_2") (pintype "unspecified"))
      (node (ref "LED9") (pin "2") (pinfunction "-_2") (pintype "unspecified"))
      (node (ref "Q1") (pin "2") (pinfunction "2_2") (pintype "input"))
      (node (ref "R1") (pin "1") (pinfunction "1_1") (pintype "input"))
      (node (ref "R12") (pin "1") (pinfunction "1_1") (pintype "input"))
      (node (ref "SW1") (pin "C") (pinfunction "C_C") (pintype "unspecified"))
      (node (ref "SW1") (pin "E") (pinfunction "E_E") (pintype "unspecified"))
      (node (ref "U11") (pin "20") (pinfunction "GND_20") (pintype "unspecified"))
      (node (ref "U13") (pin "1") (pinfunction "1_1") (pintype "unspecified"))
      (node (ref "U14") (pin "1") (pinfunction "1_1") (pintype "unspecified"))
      (node (ref "U15") (pin "1") (pinfunction "1_1") (pintype "unspecified"))
      (node (ref "U16") (pin "1") (pinfunction "A1_1") (pintype "unspecified"))
      (node (ref "U16") (pin "2") (pinfunction "A0_2") (pintype "unspecified"))
      (node (ref "U16") (pin "6") (pinfunction "GND_6") (pintype "unspecified"))
      (node (ref "U17") (pin "1") (pinfunction "A0_1") (pintype "unspecified"))
      (node (ref "U17") (pin "2") (pinfunction "A1_2") (pintype "unspecified"))
      (node (ref "U17") (pin "3") (pinfunction "A2_3") (pintype "unspecified"))
      (node (ref "U17") (pin "8") (pinfunction "VSS_8") (pintype "unspecified"))
      (node (ref "U18") (pin "20") (pinfunction "GND_20") (pintype "unspecified"))
      (node (ref "U19") (pin "1") (pinfunction "1_1") (pintype "unspecified"))
      (node (ref "U2") (pin "2") (pinfunction "2_2") (pintype "unspecified"))
      (node (ref "U20") (pin "1") (pinfunction "1_1") (pintype "unspecified"))
      (node (ref "U21") (pin "8") (pinfunction "VSS_8") (pintype "unspecified"))
      (node (ref "U22") (pin "1") (pinfunction "1_1") (pintype "unspecified"))
      (node (ref "U23") (pin "1") (pinfunction "1_1") (pintype "unspecified"))
      (node (ref "U24") (pin "10") (pinfunction "PGND2_10") (pintype "unspecified"))
      (node (ref "U24") (pin "18") (pinfunction "GND_18") (pintype "unspecified"))
      (node (ref "U24") (pin "3") (pinfunction "PGND1_3") (pintype "unspecified"))
      (node (ref "U24") (pin "4") (pinfunction "PGND1_4") (pintype "unspecified"))
      (node (ref "U24") (pin "9") (pinfunction "PGND2_9") (pintype "unspecified"))
      (node (ref "U25") (pin "10") (pinfunction "PGND2_10") (pintype "unspecified"))
      (node (ref "U25") (pin "18") (pinfunction "GND_18") (pintype "unspecified"))
      (node (ref "U25") (pin "3") (pinfunction "PGND1_3") (pintype "unspecified"))
      (node (ref "U25") (pin "4") (pinfunction "PGND1_4") (pintype "unspecified"))
      (node (ref "U25") (pin "9") (pinfunction "PGND2_9") (pintype "unspecified"))
      (node (ref "U26") (pin "10") (pinfunction "PGND2_10") (pintype "unspecified"))
      (node (ref "U26") (pin "18") (pinfunction "GND_18") (pintype "unspecified"))
      (node (ref "U26") (pin "3") (pinfunction "PGND1_3") (pintype "unspecified"))
      (node (ref "U26") (pin "4") (pinfunction "PGND1_4") (pintype "unspecified"))
      (node (ref "U26") (pin "9") (pinfunction "PGND2_9") (pintype "unspecified"))
      (node (ref "U27") (pin "10") (pinfunction "PGND2_10") (pintype "unspecified"))
      (node (ref "U27") (pin "18") (pinfunction "GND_18") (pintype "unspecified"))
      (node (ref "U27") (pin "3") (pinfunction "PGND1_3") (pintype "unspecified"))
      (node (ref "U27") (pin "4") (pinfunction "PGND1_4") (pintype "unspecified"))
      (node (ref "U27") (pin "9") (pinfunction "PGND2_9") (pintype "unspecified"))
      (node (ref "U28") (pin "1") (pinfunction "1_1") (pintype "unspecified"))
      (node (ref "U29") (pin "1") (pinfunction "1_1") (pintype "unspecified"))
      (node (ref "U3") (pin "2") (pinfunction "2_2") (pintype "unspecified"))
      (node (ref "U4") (pin "2") (pinfunction "2_2") (pintype "unspecified"))
      (node (ref "U6") (pin "2") (pinfunction "GND_2") (pintype "unspecified"))
      (node (ref "U7") (pin "2") (pinfunction "A_2") (pintype "unspecified"))
      (node (ref "U8") (pin "13") (pinfunction "-V_13") (pintype "unspecified"))
      (node (ref "U9") (pin "12") (pinfunction "KNX_B_12") (pintype "unspecified"))
      (node (ref "U9") (pin "16") (pinfunction "DCDC_GND_16") (pintype "unspecified"))
      (node (ref "U9") (pin "25") (pinfunction "EP_25") (pintype "unspecified"))
      (node (ref "U9") (pin "4") (pinfunction "KNX_B_4") (pintype "unspecified"))
    )
    (net (code "16") (name "IN_1") (class "Default")
      (node (ref "R21") (pin "2") (pinfunction "2_2") (pintype "input"))
      (node (ref "U11") (pin "5") (pinfunction "PA7_5") (pintype "unspecified"))
      (node (ref "U24") (pin "17") (pinfunction "BIN1_17") (pintype "unspecified"))
      (node (ref "U24") (pin "21") (pinfunction "AIN1_21") (pintype "unspecified"))
      (node (ref "U25") (pin "17") (pinfunction "BIN1_17") (pintype "unspecified"))
      (node (ref "U25") (pin "21") (pinfunction "AIN1_21") (pintype "unspecified"))
      (node (ref "U26") (pin "17") (pinfunction "BIN1_17") (pintype "unspecified"))
      (node (ref "U26") (pin "21") (pinfunction "AIN1_21") (pintype "unspecified"))
      (node (ref "U27") (pin "17") (pinfunction "BIN1_17") (pintype "unspecified"))
      (node (ref "U27") (pin "21") (pinfunction "AIN1_21") (pintype "unspecified"))
    )
    (net (code "17") (name "IN_2") (class "Default")
      (node (ref "R25") (pin "2") (pinfunction "2_2") (pintype "input"))
      (node (ref "U11") (pin "6") (pinfunction "PB5_6") (pintype "unspecified"))
      (node (ref "U24") (pin "16") (pinfunction "BIN2_16") (pintype "unspecified"))
      (node (ref "U24") (pin "22") (pinfunction "AIN2_22") (pintype "unspecified"))
      (node (ref "U25") (pin "16") (pinfunction "BIN2_16") (pintype "unspecified"))
      (node (ref "U25") (pin "22") (pinfunction "AIN2_22") (pintype "unspecified"))
      (node (ref "U26") (pin "16") (pinfunction "BIN2_16") (pintype "unspecified"))
      (node (ref "U26") (pin "22") (pinfunction "AIN2_22") (pintype "unspecified"))
      (node (ref "U27") (pin "16") (pinfunction "BIN2_16") (pintype "unspecified"))
      (node (ref "U27") (pin "22") (pinfunction "AIN2_22") (pintype "unspecified"))
    )
    (net (code "18") (name "KNC_AC") (class "Default")
      (node (ref "C4") (pin "2") (pinfunction "2_2") (pintype "input"))
      (node (ref "U7") (pin "1") (pinfunction "K_1") (pintype "unspecified"))
      (node (ref "U9") (pin "2") (pinfunction "KNX_AC_2") (pintype "unspecified"))
    )
    (net (code "19") (name "KNX+") (class "Default")
      (node (ref "C13") (pin "1") (pinfunction "1_1") (pintype "input"))
      (node (ref "D5") (pin "1") (pinfunction "1_1") (pintype "unspecified"))
      (node (ref "R1") (pin "2") (pinfunction "2_2") (pintype "input"))
      (node (ref "U1") (pin "2") (pinfunction "A_2") (pintype "unspecified"))
      (node (ref "U3") (pin "1") (pinfunction "1_1") (pintype "unspecified"))
      (node (ref "U4") (pin "1") (pinfunction "1_1") (pintype "unspecified"))
    )
    (net (code "20") (name "KNX_A") (class "Default")
      (node (ref "C4") (pin "1") (pinfunction "1_1") (pintype "input"))
      (node (ref "C7") (pin "1") (pinfunction "1_1") (pintype "input"))
      (node (ref "U1") (pin "1") (pinfunction "K_1") (pintype "unspecified"))
      (node (ref "U12") (pin "2") (pinfunction "2_2") (pintype "unspecified"))
      (node (ref "U9") (pin "11") (pinfunction "KNX_A_11") (pintype "unspecified"))
    )
    (net (code "21") (name "KNX_OK") (class "Default")
      (node (ref "U11") (pin "19") (pinfunction "PA3/EXTCLK_19") (pintype "unspecified"))
      (node (ref "U9") (pin "21") (pinfunction "KNX_OK_21") (pintype "unspecified"))
    )
    (net (code "22") (name "KNX_Rx") (class "Default")
      (node (ref "R46") (pin "1") (pinfunction "1_1") (pintype "input"))
      (node (ref "U11") (pin "18") (pinfunction "PA2_18") (pintype "unspecified"))
      (node (ref "U9") (pin "23") (pinfunction "KNX_RX_23") (pintype "unspecified"))
    )
    (net (code "23") (name "KNX_Tx") (class "Default")
      (node (ref "R45") (pin "1") (pinfunction "1_1") (pintype "input"))
      (node (ref "U11") (pin "17") (pinfunction "PA1_17") (pintype "unspecified"))
      (node (ref "U9") (pin "24") (pinfunction "KNX_TX_24") (pintype "unspecified"))
    )
    (net (code "24") (name "L") (class "Default")
      (node (ref "F1") (pin "2") (pinfunction "2_2") (pintype "unspecified"))
      (node (ref "U8") (pin "1") (pinfunction "AC/L_1") (pintype "unspecified"))
    )
    (net (code "25") (name "LED_1") (class "Default")
      (node (ref "R17") (pin "2") (pinfunction "2_2") (pintype "input"))
      (node (ref "U11") (pin "15") (pinfunction "PC3_15") (pintype "unspecified"))
    )
    (net (code "26") (name "LED_2") (class "Default")
      (node (ref "R30") (pin "2") (pinfunction "2_2") (pintype "input"))
      (node (ref "U18") (pin "15") (pinfunction "PC3_15") (pintype "unspecified"))
    )
    (net (code "27") (name "M1+") (class "Default")
      (node (ref "U27") (pin "1") (pinfunction "AO1_1") (pintype "unspecified"))
      (node (ref "U27") (pin "2") (pinfunction "AO1_2") (pintype "unspecified"))
      (node (ref "U36") (pin "1") (pinfunction "1_1") (pintype "unspecified"))
    )
    (net (code "28") (name "M1-") (class "Default")
      (node (ref "U27") (pin "5") (pinfunction "AO2_5") (pintype "unspecified"))
      (node (ref "U27") (pin "6") (pinfunction "AO2_6") (pintype "unspecified"))
      (node (ref "U36") (pin "2") (pinfunction "2_2") (pintype "unspecified"))
    )
    (net (code "29") (name "M1_EN") (class "Default")
      (node (ref "R35") (pin "2") (pinfunction "2_2") (pintype "input"))
      (node (ref "U17") (pin "4") (pinfunction "P0_4") (pintype "unspecified"))
      (node (ref "U27") (pin "23") (pinfunction "PWMA_23") (pintype "unspecified"))
    )
    (net (code "30") (name "M2+") (class "Default")
      (node (ref "U27") (pin "11") (pinfunction "BO1_11") (pintype "unspecified"))
      (node (ref "U27") (pin "12") (pinfunction "BO1_12") (pintype "unspecified"))
      (node (ref "U37") (pin "1") (pinfunction "1_1") (pintype "unspecified"))
    )
    (net (code "31") (name "M2-") (class "Default")
      (node (ref "U27") (pin "7") (pinfunction "BO2_7") (pintype "unspecified"))
      (node (ref "U27") (pin "8") (pinfunction "BO2_8") (pintype "unspecified"))
      (node (ref "U37") (pin "2") (pinfunction "2_2") (pintype "unspecified"))
    )
    (net (code "32") (name "M2_EN") (class "Default")
      (node (ref "R40") (pin "2") (pinfunction "2_2") (pintype "input"))
      (node (ref "U17") (pin "5") (pinfunction "P1_5") (pintype "unspecified"))
      (node (ref "U27") (pin "15") (pinfunction "PWMB_15") (pintype "unspecified"))
    )
    (net (code "33") (name "M3+") (class "Default")
      (node (ref "U26") (pin "1") (pinfunction "AO1_1") (pintype "unspecified"))
      (node (ref "U26") (pin "2") (pinfunction "AO1_2") (pintype "unspecified"))
      (node (ref "U34") (pin "1") (pinfunction "1_1") (pintype "unspecified"))
    )
    (net (code "34") (name "M3-") (class "Default")
      (node (ref "U26") (pin "5") (pinfunction "AO2_5") (pintype "unspecified"))
      (node (ref "U26") (pin "6") (pinfunction "AO2_6") (pintype "unspecified"))
      (node (ref "U34") (pin "2") (pinfunction "2_2") (pintype "unspecified"))
    )
    (net (code "35") (name "M3_EN") (class "Default")
      (node (ref "R34") (pin "2") (pinfunction "2_2") (pintype "input"))
      (node (ref "U17") (pin "6") (pinfunction "P2_6") (pintype "unspecified"))
      (node (ref "U26") (pin "23") (pinfunction "PWMA_23") (pintype "unspecified"))
    )
    (net (code "36") (name "M4+") (class "Default")
      (node (ref "U26") (pin "11") (pinfunction "BO1_11") (pintype "unspecified"))
      (node (ref "U26") (pin "12") (pinfunction "BO1_12") (pintype "unspecified"))
      (node (ref "U35") (pin "1") (pinfunction "1_1") (pintype "unspecified"))
    )
    (net (code "37") (name "M4-") (class "Default")
      (node (ref "U26") (pin "7") (pinfunction "BO2_7") (pintype "unspecified"))
      (node (ref "U26") (pin "8") (pinfunction "BO2_8") (pintype "unspecified"))
      (node (ref "U35") (pin "2") (pinfunction "2_2") (pintype "unspecified"))
    )
    (net (code "38") (name "M4_EN") (class "Default")
      (node (ref "R39") (pin "2") (pinfunction "2_2") (pintype "input"))
      (node (ref "U17") (pin "7") (pinfunction "P3_7") (pintype "unspecified"))
      (node (ref "U26") (pin "15") (pinfunction "PWMB_15") (pintype "unspecified"))
    )
    (net (code "39") (name "M5+") (class "Default")
      (node (ref "U24") (pin "1") (pinfunction "AO1_1") (pintype "unspecified"))
      (node (ref "U24") (pin "2") (pinfunction "AO1_2") (pintype "unspecified"))
      (node (ref "U30") (pin "1") (pinfunction "1_1") (pintype "unspecified"))
    )
    (net (code "40") (name "M5-") (class "Default")
      (node (ref "U24") (pin "5") (pinfunction "AO2_5") (pintype "unspecified"))
      (node (ref "U24") (pin "6") (pinfunction "AO2_6") (pintype "unspecified"))
      (node (ref "U30") (pin "2") (pinfunction "2_2") (pintype "unspecified"))
    )
    (net (code "41") (name "M5_EN") (class "Default")
      (node (ref "R32") (pin "2") (pinfunction "2_2") (pintype "input"))
      (node (ref "U17") (pin "9") (pinfunction "P4_9") (pintype "unspecified"))
      (node (ref "U24") (pin "23") (pinfunction "PWMA_23") (pintype "unspecified"))
    )
    (net (code "42") (name "M6+") (class "Default")
      (node (ref "U24") (pin "11") (pinfunction "BO1_11") (pintype "unspecified"))
      (node (ref "U24") (pin "12") (pinfunction "BO1_12") (pintype "unspecified"))
      (node (ref "U31") (pin "1") (pinfunction "1_1") (pintype "unspecified"))
    )
    (net (code "43") (name "M6-") (class "Default")
      (node (ref "U24") (pin "7") (pinfunction "BO2_7") (pintype "unspecified"))
      (node (ref "U24") (pin "8") (pinfunction "BO2_8") (pintype "unspecified"))
      (node (ref "U31") (pin "2") (pinfunction "2_2") (pintype "unspecified"))
    )
    (net (code "44") (name "M6_EN") (class "Default")
      (node (ref "R37") (pin "2") (pinfunction "2_2") (pintype "input"))
      (node (ref "U17") (pin "10") (pinfunction "P5_10") (pintype "unspecified"))
      (node (ref "U24") (pin "15") (pinfunction "PWMB_15") (pintype "unspecified"))
    )
    (net (code "45") (name "M7+") (class "Default")
      (node (ref "U25") (pin "1") (pinfunction "AO1_1") (pintype "unspecified"))
      (node (ref "U25") (pin "2") (pinfunction "AO1_2") (pintype "unspecified"))
      (node (ref "U32") (pin "1") (pinfunction "1_1") (pintype "unspecified"))
    )
    (net (code "46") (name "M7-") (class "Default")
      (node (ref "U25") (pin "5") (pinfunction "AO2_5") (pintype "unspecified"))
      (node (ref "U25") (pin "6") (pinfunction "AO2_6") (pintype "unspecified"))
      (node (ref "U32") (pin "2") (pinfunction "2_2") (pintype "unspecified"))
    )
    (net (code "47") (name "M7_EN") (class "Default")
      (node (ref "R33") (pin "2") (pinfunction "2_2") (pintype "input"))
      (node (ref "U17") (pin "11") (pinfunction "P6_11") (pintype "unspecified"))
      (node (ref "U25") (pin "23") (pinfunction "PWMA_23") (pintype "unspecified"))
    )
    (net (code "48") (name "M8+") (class "Default")
      (node (ref "U25") (pin "11") (pinfunction "BO1_11") (pintype "unspecified"))
      (node (ref "U25") (pin "12") (pinfunction "BO1_12") (pintype "unspecified"))
      (node (ref "U33") (pin "1") (pinfunction "1_1") (pintype "unspecified"))
    )
    (net (code "49") (name "M8-") (class "Default")
      (node (ref "U25") (pin "7") (pinfunction "BO2_7") (pintype "unspecified"))
      (node (ref "U25") (pin "8") (pinfunction "BO2_8") (pintype "unspecified"))
      (node (ref "U33") (pin "2") (pinfunction "2_2") (pintype "unspecified"))
    )
    (net (code "50") (name "M8_EN") (class "Default")
      (node (ref "R38") (pin "2") (pinfunction "2_2") (pintype "input"))
      (node (ref "U17") (pin "12") (pinfunction "P7_12") (pintype "unspecified"))
      (node (ref "U25") (pin "15") (pinfunction "PWMB_15") (pintype "unspecified"))
    )
    (net (code "51") (name "MISO") (class "Default")
      (node (ref "R22") (pin "1") (pinfunction "1_1") (pintype "input"))
      (node (ref "U11") (pin "13") (pinfunction "PC1_13") (pintype "unspecified"))
      (node (ref "U18") (pin "17") (pinfunction "PA1_17") (pintype "unspecified"))
    )
    (net (code "52") (name "MOSI") (class "Default")
      (node (ref "R26") (pin "1") (pinfunction "1_1") (pintype "input"))
      (node (ref "U11") (pin "14") (pinfunction "PC2_14") (pintype "unspecified"))
      (node (ref "U18") (pin "18") (pinfunction "PA2_18") (pintype "unspecified"))
    )
    (net (code "53") (name "M_VCC") (class "Default")
      (node (ref "C19") (pin "1") (pinfunction "1_1") (pintype "input"))
      (node (ref "C25") (pin "2") (pinfunction "2_2") (pintype "input"))
      (node (ref "C26") (pin "2") (pinfunction "2_2") (pintype "input"))
      (node (ref "C27") (pin "2") (pinfunction "2_2") (pintype "input"))
      (node (ref "C28") (pin "2") (pinfunction "2_2") (pintype "input"))
      (node (ref "C29") (pin "2") (pinfunction "2_2") (pintype "input"))
      (node (ref "C30") (pin "2") (pinfunction "2_2") (pintype "input"))
      (node (ref "C31") (pin "2") (pinfunction "2_2") (pintype "input"))
      (node (ref "C32") (pin "2") (pinfunction "2_2") (pintype "input"))
      (node (ref "R18") (pin "2") (pinfunction "2_2") (pintype "unspecified"))
      (node (ref "R24") (pin "2") (pinfunction "2_2") (pintype "input"))
      (node (ref "U24") (pin "13") (pinfunction "VM2_13") (pintype "unspecified"))
      (node (ref "U24") (pin "14") (pinfunction "VM3_14") (pintype "unspecified"))
      (node (ref "U24") (pin "24") (pinfunction "VM1_24") (pintype "unspecified"))
      (node (ref "U25") (pin "13") (pinfunction "VM2_13") (pintype "unspecified"))
      (node (ref "U25") (pin "14") (pinfunction "VM3_14") (pintype "unspecified"))
      (node (ref "U25") (pin "24") (pinfunction "VM1_24") (pintype "unspecified"))
      (node (ref "U26") (pin "13") (pinfunction "VM2_13") (pintype "unspecified"))
      (node (ref "U26") (pin "14") (pinfunction "VM3_14") (pintype "unspecified"))
      (node (ref "U26") (pin "24") (pinfunction "VM1_24") (pintype "unspecified"))
      (node (ref "U27") (pin "13") (pinfunction "VM2_13") (pintype "unspecified"))
      (node (ref "U27") (pin "14") (pinfunction "VM3_14") (pintype "unspecified"))
      (node (ref "U27") (pin "24") (pinfunction "VM1_24") (pintype "unspecified"))
    )
    (net (code "54") (name "N") (class "Default")
      (node (ref "U5") (pin "3") (pinfunction "3_3") (pintype "unspecified"))
      (node (ref "U8") (pin "24") (pinfunction "AC/N_24") (pintype "unspecified"))
    )
    (net (code "55") (name "Net-(C9-Pad2)") (class "Default")
      (node (ref "C9") (pin "2") (pinfunction "2_2") (pintype "input"))
      (node (ref "R7") (pin "1") (pinfunction "1_1") (pintype "input"))
    )
    (net (code "56") (name "Net-(C13-Pad2)") (class "Default")
      (node (ref "C13") (pin "2") (pinfunction "2_2") (pintype "input"))
      (node (ref "R8") (pin "1") (pinfunction "1_1") (pintype "input"))
    )
    (net (code "57") (name "Net-(D1-K)") (class "Default")
      (node (ref "D1") (pin "1") (pinfunction "K_1") (pintype "unspecified"))
      (node (ref "U6") (pin "1") (pinfunction "+Vin_1") (pintype "unspecified"))
    )
    (net (code "58") (name "Net-(F1-Pad1)") (class "Default")
      (node (ref "F1") (pin "1") (pinfunction "1_1") (pintype "unspecified"))
      (node (ref "U5") (pin "1") (pinfunction "1_1") (pintype "unspecified"))
    )
    (net (code "59") (name "Net-(LCD1-BLK)") (class "Default")
      (node (ref "LCD1") (pin "16") (pinfunction "BLK_16") (pintype "unspecified"))
      (node (ref "Q1") (pin "3") (pinfunction "3_3") (pintype "input"))
    )
    (net (code "60") (name "Net-(LCD1-DB4)") (class "Default")
      (node (ref "LCD1") (pin "11") (pinfunction "DB4_11") (pintype "unspecified"))
      (node (ref "U21") (pin "9") (pinfunction "P4_9") (pintype "unspecified"))
    )
    (net (code "61") (name "Net-(LCD1-DB5)") (class "Default")
      (node (ref "LCD1") (pin "12") (pinfunction "DB5_12") (pintype "unspecified"))
      (node (ref "U21") (pin "10") (pinfunction "P5_10") (pintype "unspecified"))
    )
    (net (code "62") (name "Net-(LCD1-DB6)") (class "Default")
      (node (ref "LCD1") (pin "13") (pinfunction "DB6_13") (pintype "unspecified"))
      (node (ref "U21") (pin "11") (pinfunction "P6_11") (pintype "unspecified"))
    )
    (net (code "63") (name "Net-(LCD1-DB7)") (class "Default")
      (node (ref "LCD1") (pin "14") (pinfunction "DB7_14") (pintype "unspecified"))
      (node (ref "U21") (pin "12") (pinfunction "P7_12") (pintype "unspecified"))
    )
    (net (code "64") (name "Net-(LCD1-E)") (class "Default")
      (node (ref "LCD1") (pin "6") (pinfunction "E_6") (pintype "unspecified"))
      (node (ref "U21") (pin "6") (pinfunction "P2_6") (pintype "unspecified"))
    )
    (net (code "65") (name "Net-(LCD1-RS)") (class "Default")
      (node (ref "LCD1") (pin "4") (pinfunction "RS_4") (pintype "unspecified"))
      (node (ref "U21") (pin "4") (pinfunction "P0_4") (pintype "unspecified"))
    )
    (net (code "66") (name "Net-(LCD1-RW)") (class "Default")
      (node (ref "LCD1") (pin "5") (pinfunction "RW_5") (pintype "unspecified"))
      (node (ref "U21") (pin "5") (pinfunction "P1_5") (pintype "unspecified"))
    )
    (net (code "67") (name "Net-(LCD1-V0)") (class "Default")
      (node (ref "D6") (pin "2") (pinfunction "2_2") (pintype "unspecified"))
      (node (ref "LCD1") (pin "3") (pinfunction "V0_3") (pintype "unspecified"))
    )
    (net (code "68") (name "Net-(LED1-+)") (class "Default")
      (node (ref "LED1") (pin "1") (pinfunction "+_1") (pintype "unspecified"))
      (node (ref "R2") (pin "1") (pinfunction "1_1") (pintype "input"))
    )
    (net (code "69") (name "Net-(LED2-+)") (class "Default")
      (node (ref "LED2") (pin "1") (pinfunction "+_1") (pintype "unspecified"))
      (node (ref "R3") (pin "1") (pinfunction "1_1") (pintype "input"))
    )
    (net (code "70") (name "Net-(LED3-+)") (class "Default")
      (node (ref "LED3") (pin "1") (pinfunction "+_1") (pintype "unspecified"))
      (node (ref "R4") (pin "1") (pinfunction "1_1") (pintype "input"))
    )
    (net (code "71") (name "Net-(LED4-+)") (class "Default")
      (node (ref "LED4") (pin "1") (pinfunction "+_1") (pintype "unspecified"))
      (node (ref "R13") (pin "1") (pinfunction "1_1") (pintype "input"))
    )
    (net (code "72") (name "Net-(LED5-+)") (class "Default")
      (node (ref "LED5") (pin "1") (pinfunction "+_1") (pintype "unspecified"))
      (node (ref "R17") (pin "1") (pinfunction "1_1") (pintype "input"))
    )
    (net (code "73") (name "Net-(LED6-+)") (class "Default")
      (node (ref "LED6") (pin "1") (pinfunction "+_1") (pintype "unspecified"))
      (node (ref "R21") (pin "1") (pinfunction "1_1") (pintype "input"))
    )
    (net (code "74") (name "Net-(LED7-+)") (class "Default")
      (node (ref "LED7") (pin "1") (pinfunction "+_1") (pintype "unspecified"))
      (node (ref "R25") (pin "1") (pinfunction "1_1") (pintype "input"))
    )
    (net (code "75") (name "Net-(LED8-+)") (class "Default")
      (node (ref "LED8") (pin "1") (pinfunction "+_1") (pintype "unspecified"))
      (node (ref "R30") (pin "1") (pinfunction "1_1") (pintype "input"))
    )
    (net (code "76") (name "Net-(LED9-+)") (class "Default")
      (node (ref "LED9") (pin "1") (pinfunction "+_1") (pintype "unspecified"))
      (node (ref "R32") (pin "1") (pinfunction "1_1") (pintype "input"))
    )
    (net (code "77") (name "Net-(LED10-+)") (class "Default")
      (node (ref "LED10") (pin "1") (pinfunction "+_1") (pintype "unspecified"))
      (node (ref "R33") (pin "1") (pinfunction "1_1") (pintype "input"))
    )
    (net (code "78") (name "Net-(LED11-+)") (class "Default")
      (node (ref "LED11") (pin "1") (pinfunction "+_1") (pintype "unspecified"))
      (node (ref "R34") (pin "1") (pinfunction "1_1") (pintype "input"))
    )
    (net (code "79") (name "Net-(LED12-+)") (class "Default")
      (node (ref "LED12") (pin "1") (pinfunction "+_1") (pintype "unspecified"))
      (node (ref "R35") (pin "1") (pinfunction "1_1") (pintype "input"))
    )
    (net (code "80") (name "Net-(LED13-+)") (class "Default")
      (node (ref "LED13") (pin "1") (pinfunction "+_1") (pintype "unspecified"))
      (node (ref "R37") (pin "1") (pinfunction "1_1") (pintype "input"))
    )
    (net (code "81") (name "Net-(LED14-+)") (class "Default")
      (node (ref "LED14") (pin "1") (pinfunction "+_1") (pintype "unspecified"))
      (node (ref "R38") (pin "1") (pinfunction "1_1") (pintype "input"))
    )
    (net (code "82") (name "Net-(LED15-+)") (class "Default")
      (node (ref "LED15") (pin "1") (pinfunction "+_1") (pintype "unspecified"))
      (node (ref "R39") (pin "1") (pinfunction "1_1") (pintype "input"))
    )
    (net (code "83") (name "Net-(LED16-+)") (class "Default")
      (node (ref "LED16") (pin "1") (pinfunction "+_1") (pintype "unspecified"))
      (node (ref "R40") (pin "1") (pinfunction "1_1") (pintype "input"))
    )
    (net (code "84") (name "Net-(U9-VREF)") (class "Default")
      (node (ref "C3") (pin "2") (pinfunction "2_2") (pintype "input"))
      (node (ref "U9") (pin "8") (pinfunction "VREF_8") (pintype "unspecified"))
    )
    (net (code "85") (name "Net-(U16-IN+)") (class "Default")
      (node (ref "R23") (pin "1") (pinfunction "1_1") (pintype "input"))
      (node (ref "U16") (pin "8") (pinfunction "IN+_8") (pintype "unspecified"))
    )
    (net (code "86") (name "Net-(U16-IN-)") (class "Default")
      (node (ref "R24") (pin "1") (pinfunction "1_1") (pintype "input"))
      (node (ref "U16") (pin "7") (pinfunction "IN-_7") (pintype "unspecified"))
    )
    (net (code "87") (name "Net-(U21-P3)") (class "Default")
      (node (ref "Q1") (pin "1") (pinfunction "1_1") (pintype "input"))
      (node (ref "R41") (pin "1") (pinfunction "1_1") (pintype "input"))
      (node (ref "U21") (pin "7") (pinfunction "P3_7") (pintype "unspecified"))
    )
    (net (code "88") (name "PE") (class "Default")
      (node (ref "JMP1") (pin "1") (pinfunction "1_1") (pintype "unspecified"))
      (node (ref "U5") (pin "2") (pinfunction "2_2") (pintype "unspecified"))
    )
    (net (code "89") (name "R68") (class "Default")
      (node (ref "U12") (pin "1") (pinfunction "1_1") (pintype "unspecified"))
      (node (ref "U9") (pin "3") (pinfunction "R68_3") (pintype "unspecified"))
    )
    (net (code "90") (name "RxD_1") (class "Default")
      (node (ref "CN1") (pin "2") (pinfunction "2_2") (pintype "unspecified"))
      (node (ref "U11") (pin "8") (pinfunction "TOSC1/PB3_8") (pintype "unspecified"))
    )
    (net (code "91") (name "RxD_2") (class "Default")
      (node (ref "CN2") (pin "2") (pinfunction "2_2") (pintype "unspecified"))
      (node (ref "U18") (pin "8") (pinfunction "TOSC1/PB3_8") (pintype "unspecified"))
    )
    (net (code "92") (name "SCK") (class "Default")
      (node (ref "R19") (pin "1") (pinfunction "1_1") (pintype "input"))
      (node (ref "U11") (pin "12") (pinfunction "PC0_12") (pintype "unspecified"))
      (node (ref "U18") (pin "19") (pinfunction "PA3/EXTCLK_19") (pintype "unspecified"))
    )
    (net (code "93") (name "SCL") (class "Default")
      (node (ref "R16") (pin "1") (pinfunction "1_1") (pintype "input"))
      (node (ref "U11") (pin "11") (pinfunction "PB0_11") (pintype "unspecified"))
      (node (ref "U16") (pin "4") (pinfunction "SCL_4") (pintype "unspecified"))
      (node (ref "U17") (pin "14") (pinfunction "SCL_14") (pintype "unspecified"))
      (node (ref "U21") (pin "14") (pinfunction "SCL_14") (pintype "unspecified"))
    )
    (net (code "94") (name "SDA") (class "Default")
      (node (ref "R15") (pin "1") (pinfunction "1_1") (pintype "input"))
      (node (ref "U11") (pin "10") (pinfunction "PB1_10") (pintype "unspecified"))
      (node (ref "U16") (pin "3") (pinfunction "SDA_3") (pintype "unspecified"))
      (node (ref "U17") (pin "15") (pinfunction "SDA_15") (pintype "unspecified"))
      (node (ref "U21") (pin "15") (pinfunction "SDA_15") (pintype "unspecified"))
    )
    (net (code "95") (name "T0") (class "Default")
      (node (ref "R14") (pin "2") (pinfunction "2_2") (pintype "input"))
      (node (ref "U13") (pin "2") (pinfunction "2_2") (pintype "unspecified"))
      (node (ref "U18") (pin "2") (pinfunction "PA4_2") (pintype "unspecified"))
    )
    (net (code "96") (name "T1") (class "Default")
      (node (ref "R20") (pin "2") (pinfunction "2_2") (pintype "input"))
      (node (ref "U14") (pin "2") (pinfunction "2_2") (pintype "unspecified"))
      (node (ref "U18") (pin "3") (pinfunction "PA5_3") (pintype "unspecified"))
    )
    (net (code "97") (name "T2") (class "Default")
      (node (ref "R27") (pin "2") (pinfunction "2_2") (pintype "input"))
      (node (ref "U15") (pin "2") (pinfunction "2_2") (pintype "unspecified"))
      (node (ref "U18") (pin "4") (pinfunction "PA6_4") (pintype "unspecified"))
    )
    (net (code "98") (name "T3") (class "Default")
      (node (ref "R29") (pin "2") (pinfunction "2_2") (pintype "input"))
      (node (ref "U18") (pin "5") (pinfunction "PA7_5") (pintype "unspecified"))
      (node (ref "U19") (pin "2") (pinfunction "2_2") (pintype "unspecified"))
    )
    (net (code "99") (name "T4") (class "Default")
      (node (ref "R31") (pin "2") (pinfunction "2_2") (pintype "input"))
      (node (ref "U18") (pin "6") (pinfunction "PB5_6") (pintype "unspecified"))
      (node (ref "U20") (pin "2") (pinfunction "2_2") (pintype "unspecified"))
    )
    (net (code "100") (name "T5") (class "Default")
      (node (ref "R36") (pin "2") (pinfunction "2_2") (pintype "input"))
      (node (ref "U18") (pin "7") (pinfunction "PB4_7") (pintype "unspecified"))
      (node (ref "U22") (pin "2") (pinfunction "2_2") (pintype "unspecified"))
    )
    (net (code "101") (name "T6") (class "Default")
      (node (ref "R42") (pin "2") (pinfunction "2_2") (pintype "input"))
      (node (ref "U18") (pin "10") (pinfunction "PB1_10") (pintype "unspecified"))
      (node (ref "U23") (pin "2") (pinfunction "2_2") (pintype "unspecified"))
    )
    (net (code "102") (name "T7") (class "Default")
      (node (ref "R43") (pin "2") (pinfunction "2_2") (pintype "input"))
      (node (ref "U18") (pin "13") (pinfunction "PC1_13") (pintype "unspecified"))
      (node (ref "U28") (pin "2") (pinfunction "2_2") (pintype "unspecified"))
    )
    (net (code "103") (name "T8") (class "Default")
      (node (ref "R44") (pin "2") (pinfunction "2_2") (pintype "input"))
      (node (ref "U18") (pin "12") (pinfunction "PC0_12") (pintype "unspecified"))
      (node (ref "U29") (pin "2") (pinfunction "2_2") (pintype "unspecified"))
    )
    (net (code "104") (name "TxD_1") (class "Default")
      (node (ref "CN1") (pin "4") (pinfunction "4_4") (pintype "unspecified"))
      (node (ref "U11") (pin "9") (pinfunction "TOSC2/PB2_9") (pintype "unspecified"))
    )
    (net (code "105") (name "TxD_2") (class "Default")
      (node (ref "CN2") (pin "4") (pinfunction "4_4") (pintype "unspecified"))
      (node (ref "U18") (pin "9") (pinfunction "TOSC2/PB2_9") (pintype "unspecified"))
    )
    (net (code "106") (name "UPDI_1") (class "Default")
      (node (ref "CN1") (pin "3") (pinfunction "3_3") (pintype "unspecified"))
      (node (ref "U11") (pin "16") (pinfunction "PA0/RESET#/UPDI_16") (pintype "unspecified"))
    )
    (net (code "107") (name "UPDI_2") (class "Default")
      (node (ref "CN2") (pin "3") (pinfunction "3_3") (pintype "unspecified"))
      (node (ref "U18") (pin "16") (pinfunction "PA0/RESET#/UPDI_16") (pintype "unspecified"))
    )
    (net (code "108") (name "VCC") (class "Default")
      (node (ref "C1") (pin "2") (pinfunction "2_2") (pintype "input"))
      (node (ref "U9") (pin "20") (pinfunction "VCCCORE_20") (pintype "unspecified"))
      (node (ref "U9") (pin "22") (pinfunction "VCC_SEL_22") (pintype "unspecified"))
    )
    (net (code "109") (name "VCC_OK") (class "Default")
      (node (ref "R4") (pin "2") (pinfunction "2_2") (pintype "input"))
      (node (ref "U9") (pin "19") (pinfunction "VCC_OK_19") (pintype "unspecified"))
    )
    (net (code "110") (name "VDDHV") (class "Default")
      (node (ref "C12") (pin "1") (pinfunction "1_1") (pintype "unspecified"))
      (node (ref "C15") (pin "1") (pinfunction "1_1") (pintype "input"))
      (node (ref "C6") (pin "1") (pinfunction "1_1") (pintype "input"))
      (node (ref "U10") (pin "1") (pinfunction "K_1") (pintype "unspecified"))
      (node (ref "U9") (pin "1") (pinfunction "VDD_REGIN_1") (pintype "unspecified"))
      (node (ref "U9") (pin "14") (pinfunction "DCDC_IN_14") (pintype "unspecified"))
      (node (ref "U9") (pin "9") (pinfunction "VDDHV_9") (pintype "unspecified"))
    )
    (net (code "111") (name "VDDHV_PD") (class "Default")
      (node (ref "U10") (pin "2") (pinfunction "A_2") (pintype "unspecified"))
      (node (ref "U9") (pin "10") (pinfunction "VDDHV_PD_10") (pintype "unspecified"))
    )
    (net (code "112") (name "VFLT") (class "Default")
      (node (ref "C6") (pin "2") (pinfunction "2_2") (pintype "input"))
      (node (ref "C8") (pin "2") (pinfunction "2_2") (pintype "input"))
      (node (ref "U9") (pin "7") (pinfunction "VFLT_7") (pintype "unspecified"))
    )
    (net (code "113") (name "VGATE") (class "Default")
      (node (ref "C7") (pin "2") (pinfunction "2_2") (pintype "input"))
      (node (ref "U9") (pin "13") (pinfunction "VGATE_13") (pintype "unspecified"))
    )
    (net (code "114") (name "unconnected-(D6-Pad3)") (class "Default")
      (node (ref "D6") (pin "3") (pinfunction "3_3") (pintype "unspecified+no_connect"))
    )
    (net (code "115") (name "unconnected-(SW1-EH-Pad6)") (class "Default")
      (node (ref "SW1") (pin "6") (pinfunction "EH_6") (pintype "unspecified+no_connect"))
    )
    (net (code "116") (name "unconnected-(SW1-EH-Pad7)") (class "Default")
      (node (ref "SW1") (pin "7") (pinfunction "EH_7") (pintype "unspecified+no_connect"))
    )
    (net (code "117") (name "unconnected-(U17-INT#-Pad13)") (class "Default")
      (node (ref "U17") (pin "13") (pinfunction "INT#_13") (pintype "unspecified+no_connect"))
    )
    (net (code "118") (name "unconnected-(U18-PB0-Pad11)") (class "Default")
      (node (ref "U18") (pin "11") (pinfunction "PB0_11") (pintype "unspecified+no_connect"))
    )
    (net (code "119") (name "unconnected-(U21-INT#-Pad13)") (class "Default")
      (node (ref "U21") (pin "13") (pinfunction "INT#_13") (pintype "unspecified+no_connect"))
    )
  )
)
